# plugwatch.net
KiCad netlist of a schematic drawn in EAGLE
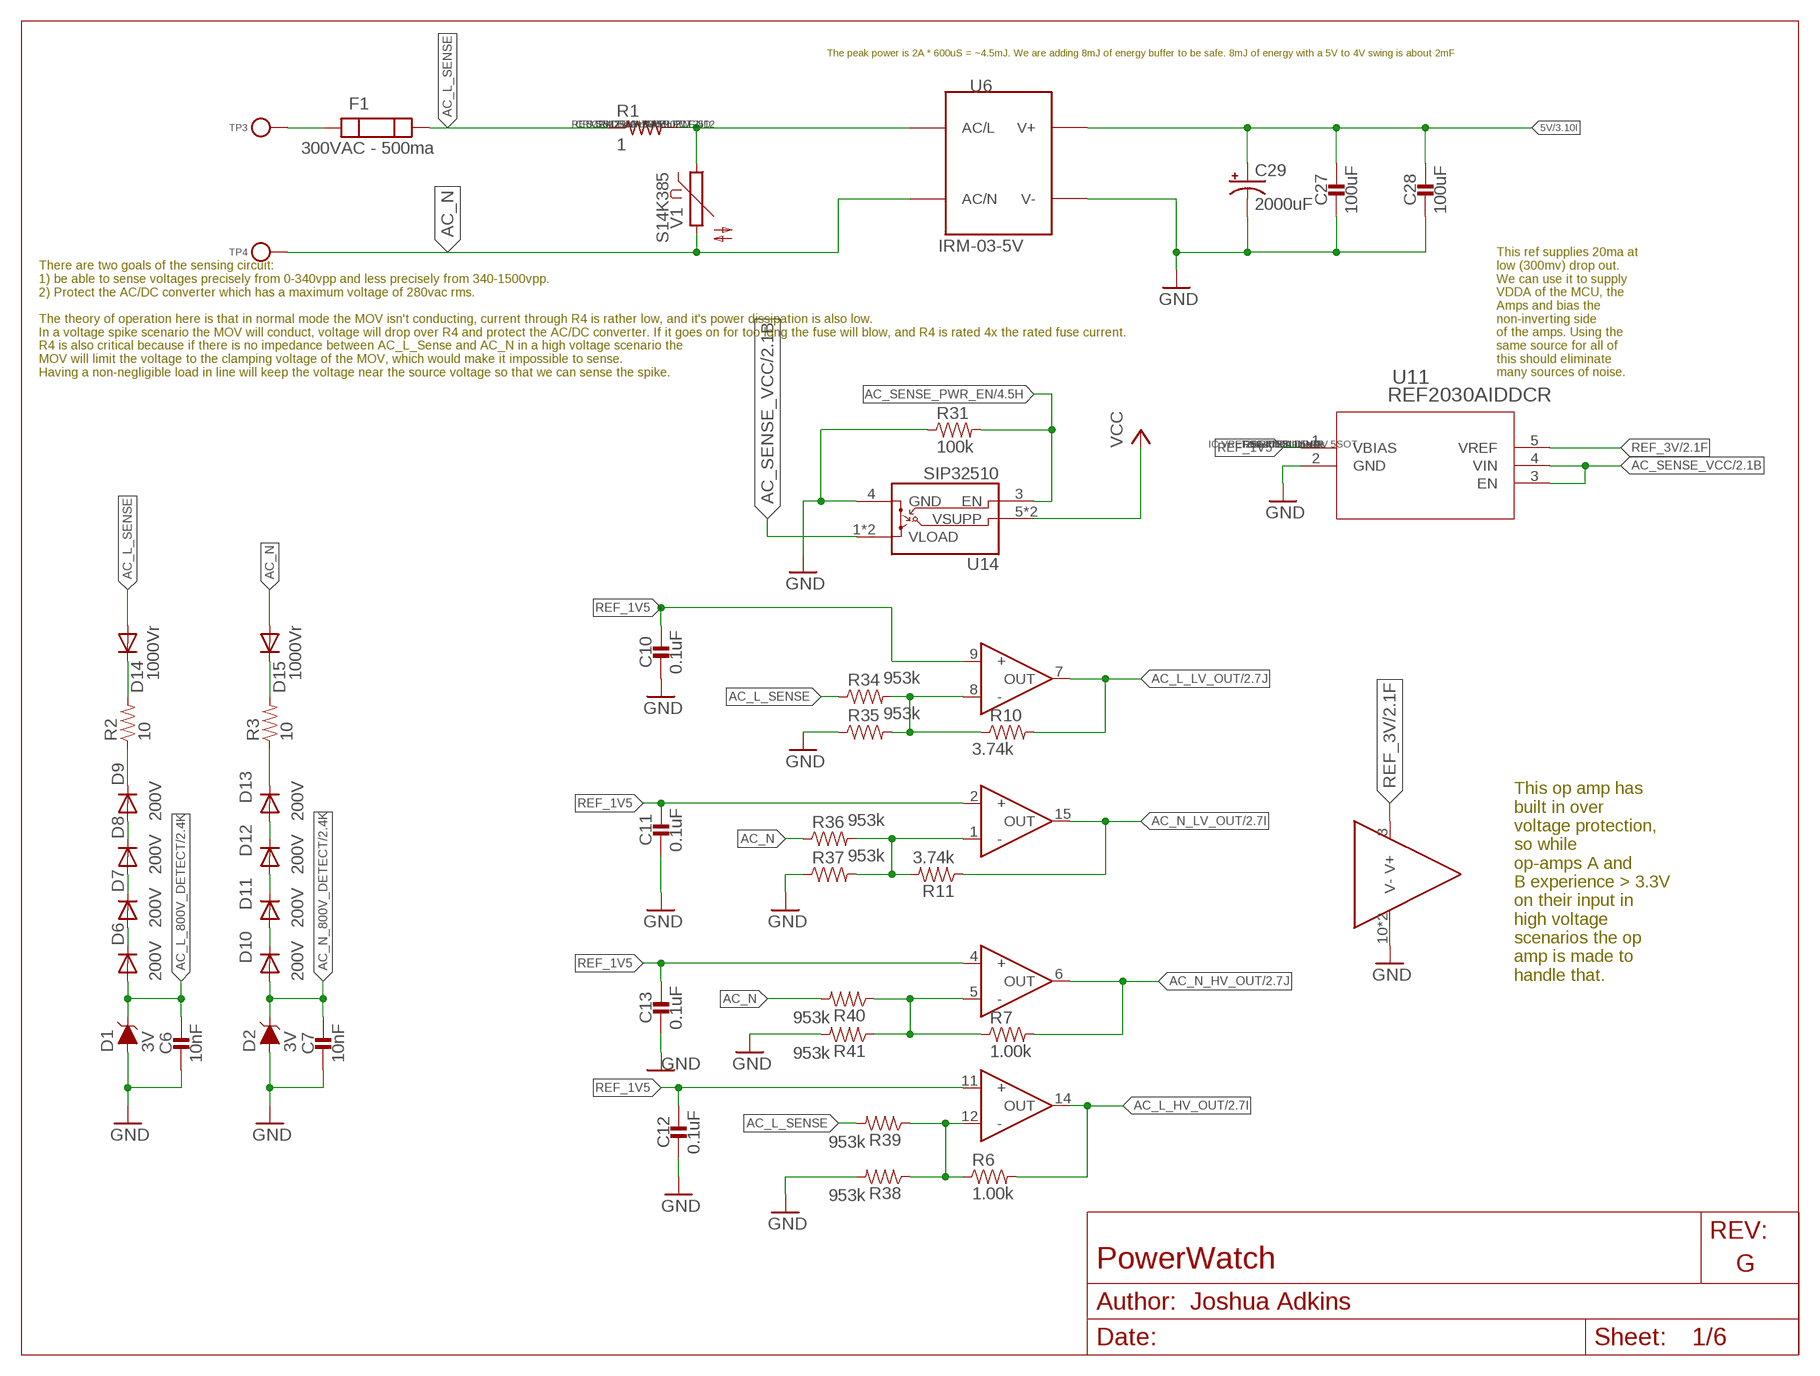
[diagram p0: schematic, sheet 1]
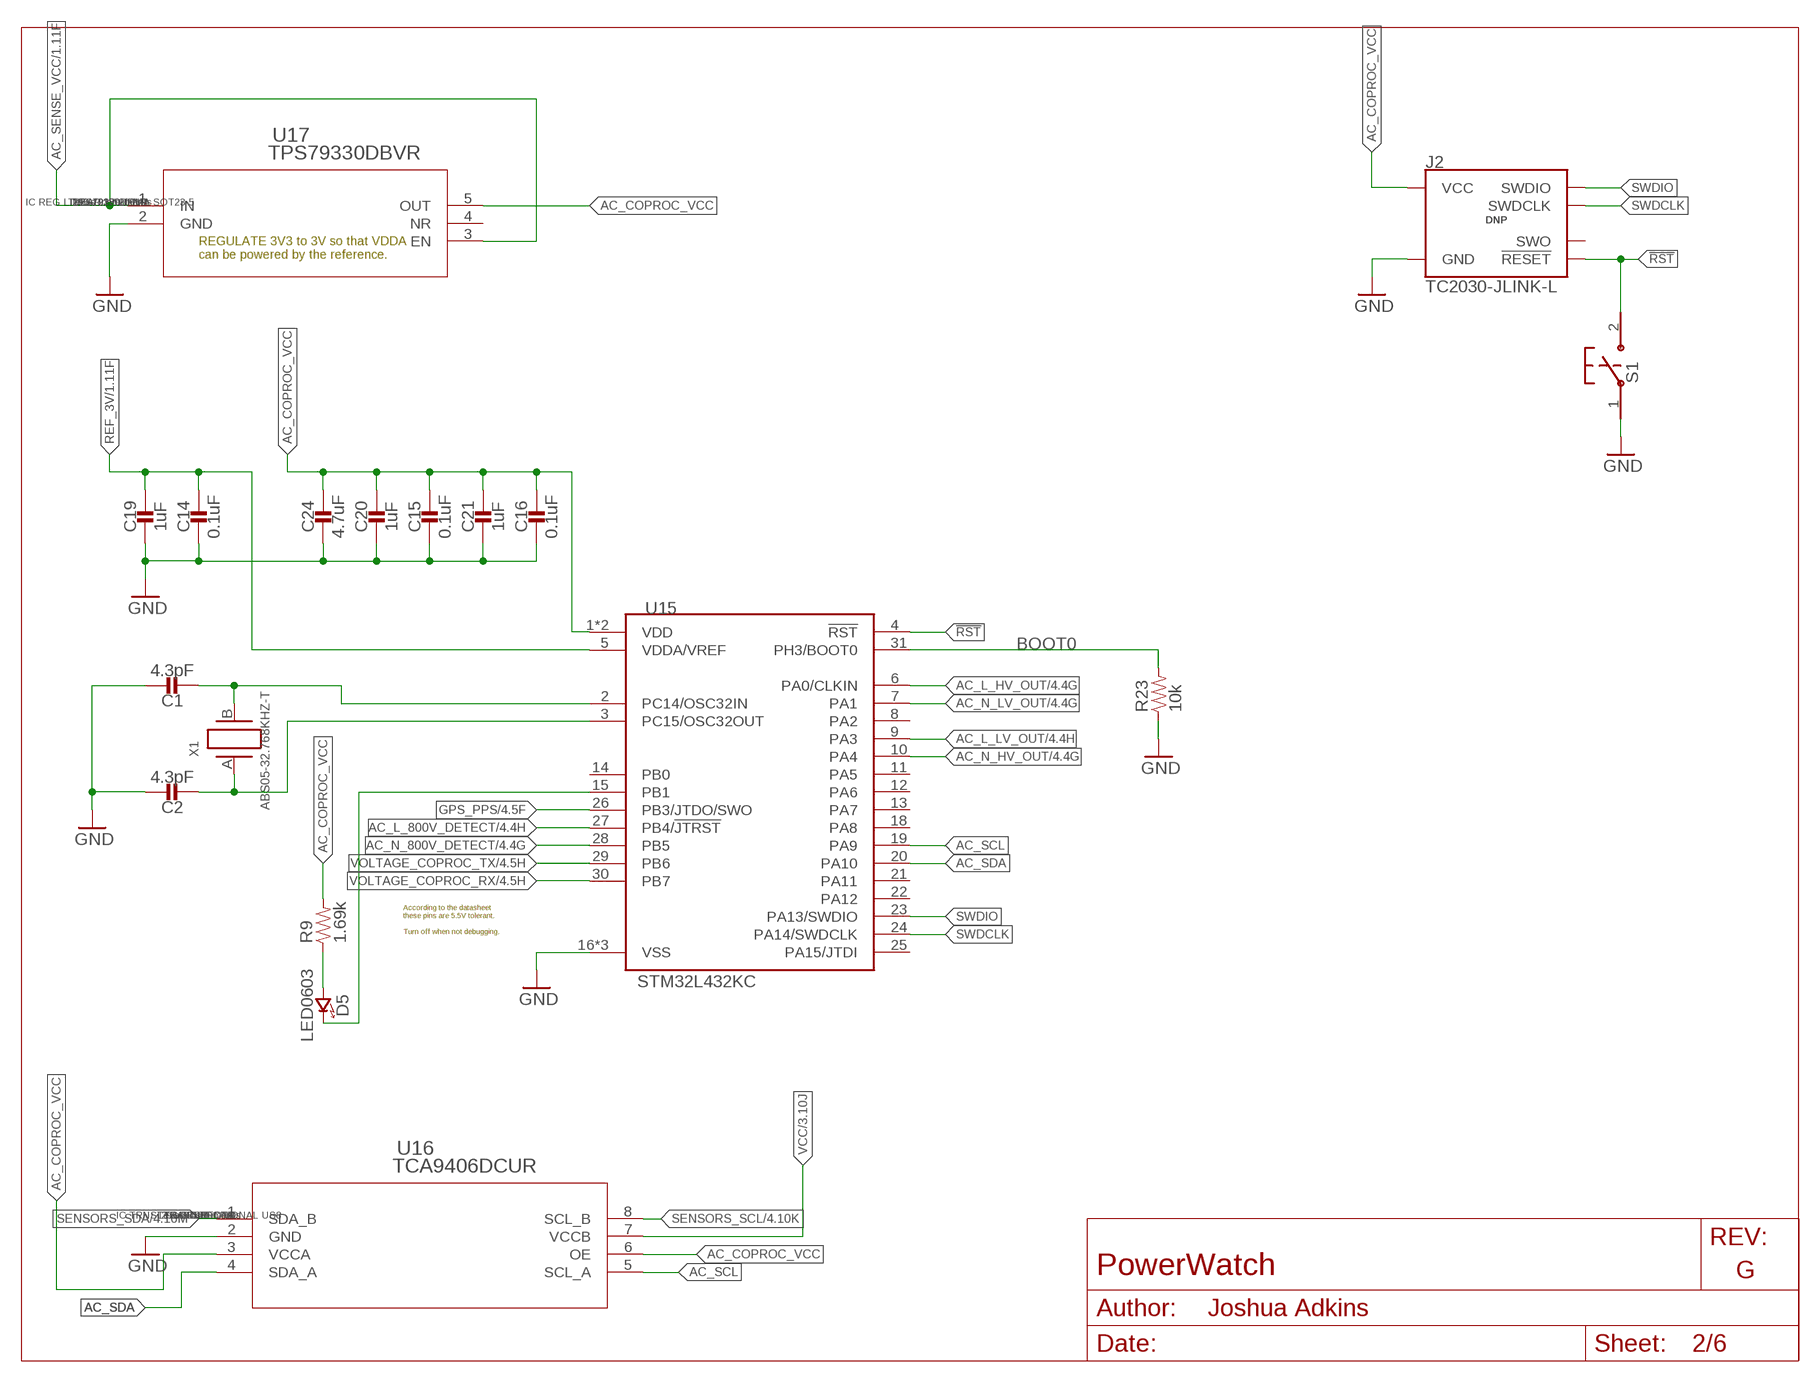
[diagram p1: schematic, sheet 2]
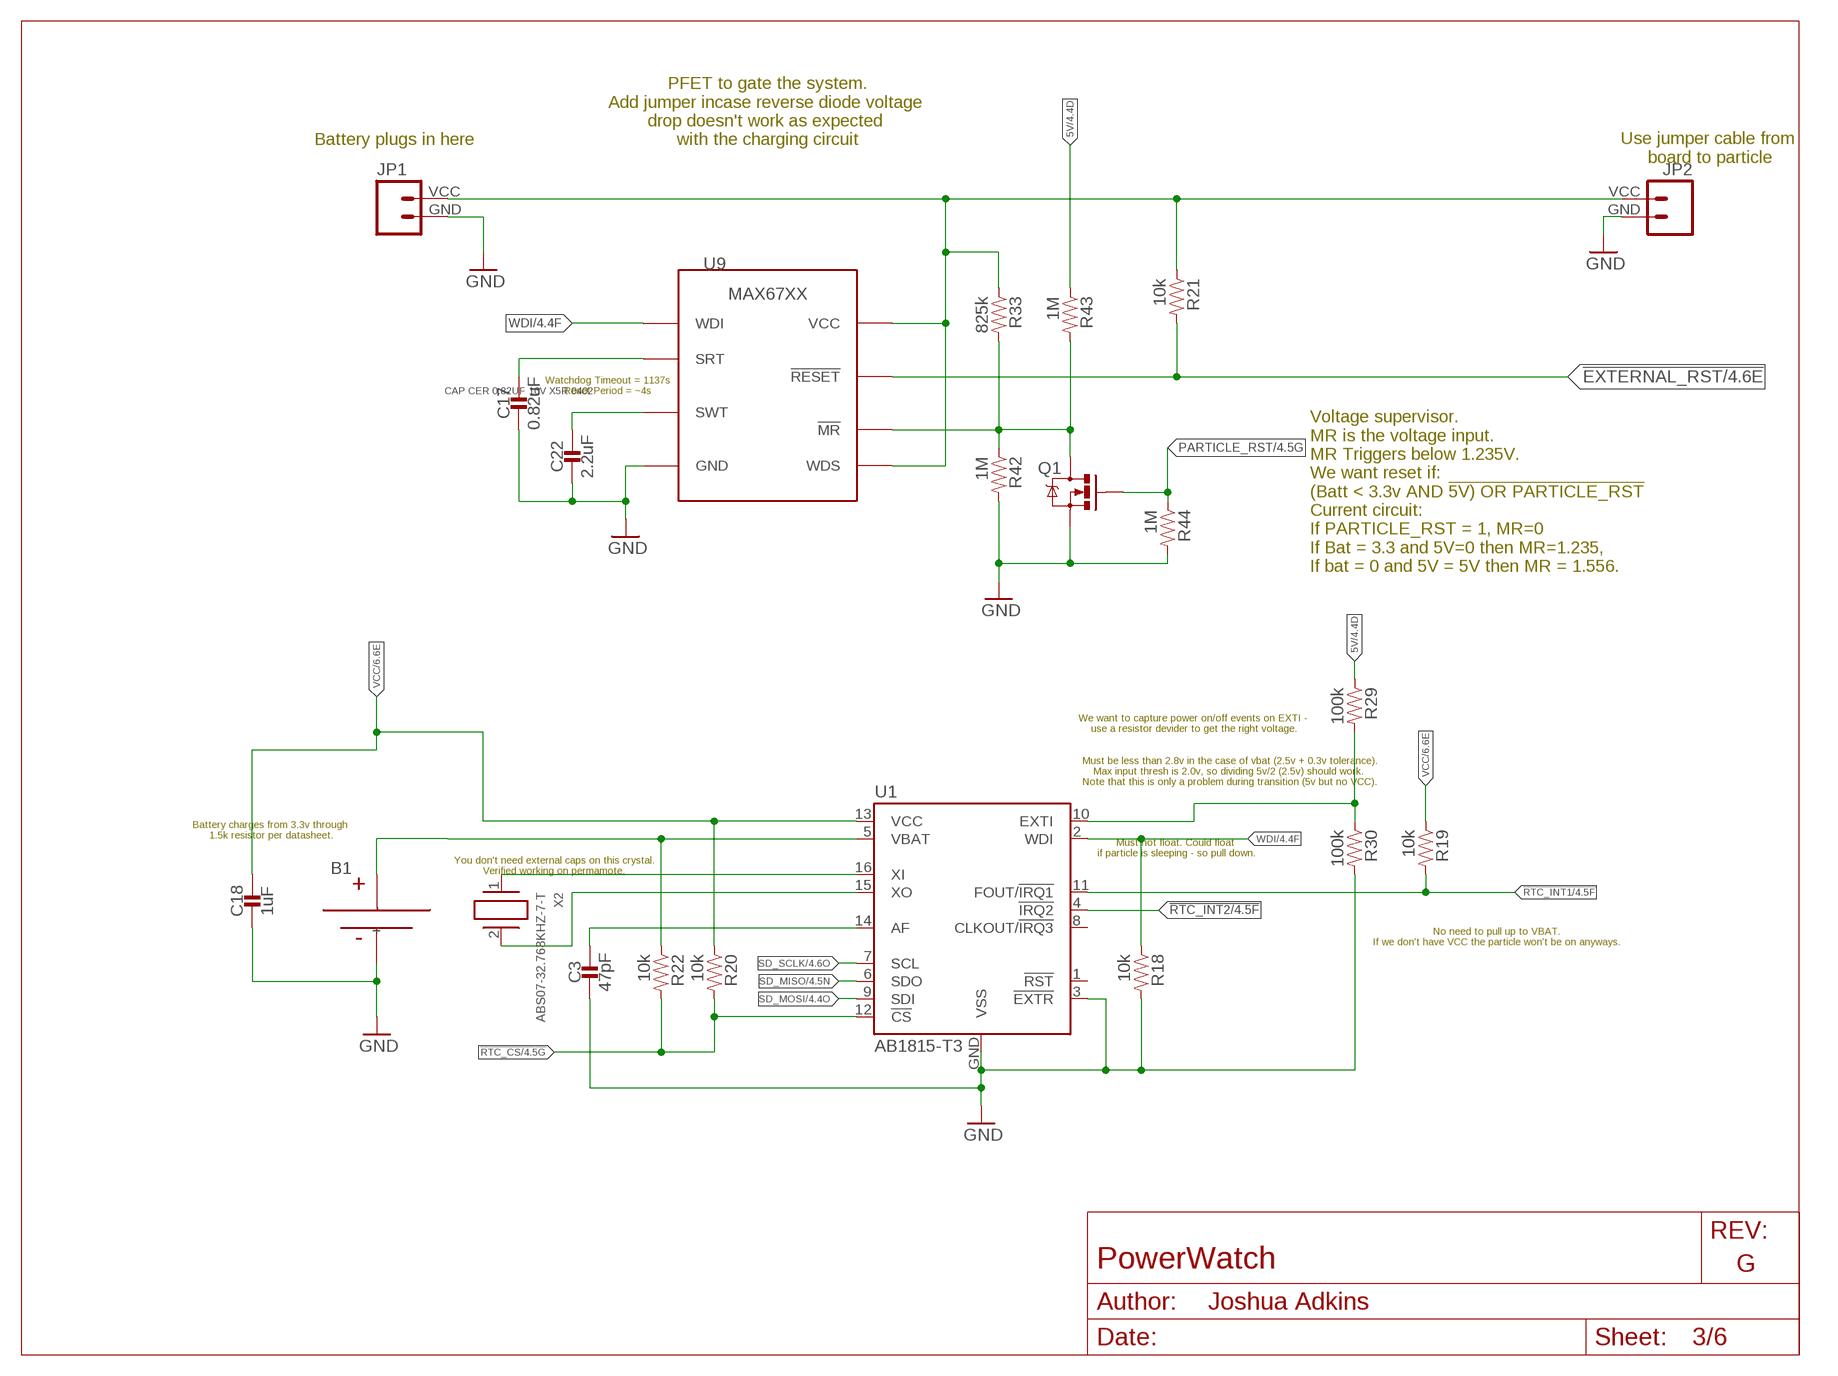
[diagram p2: schematic, sheet 3]
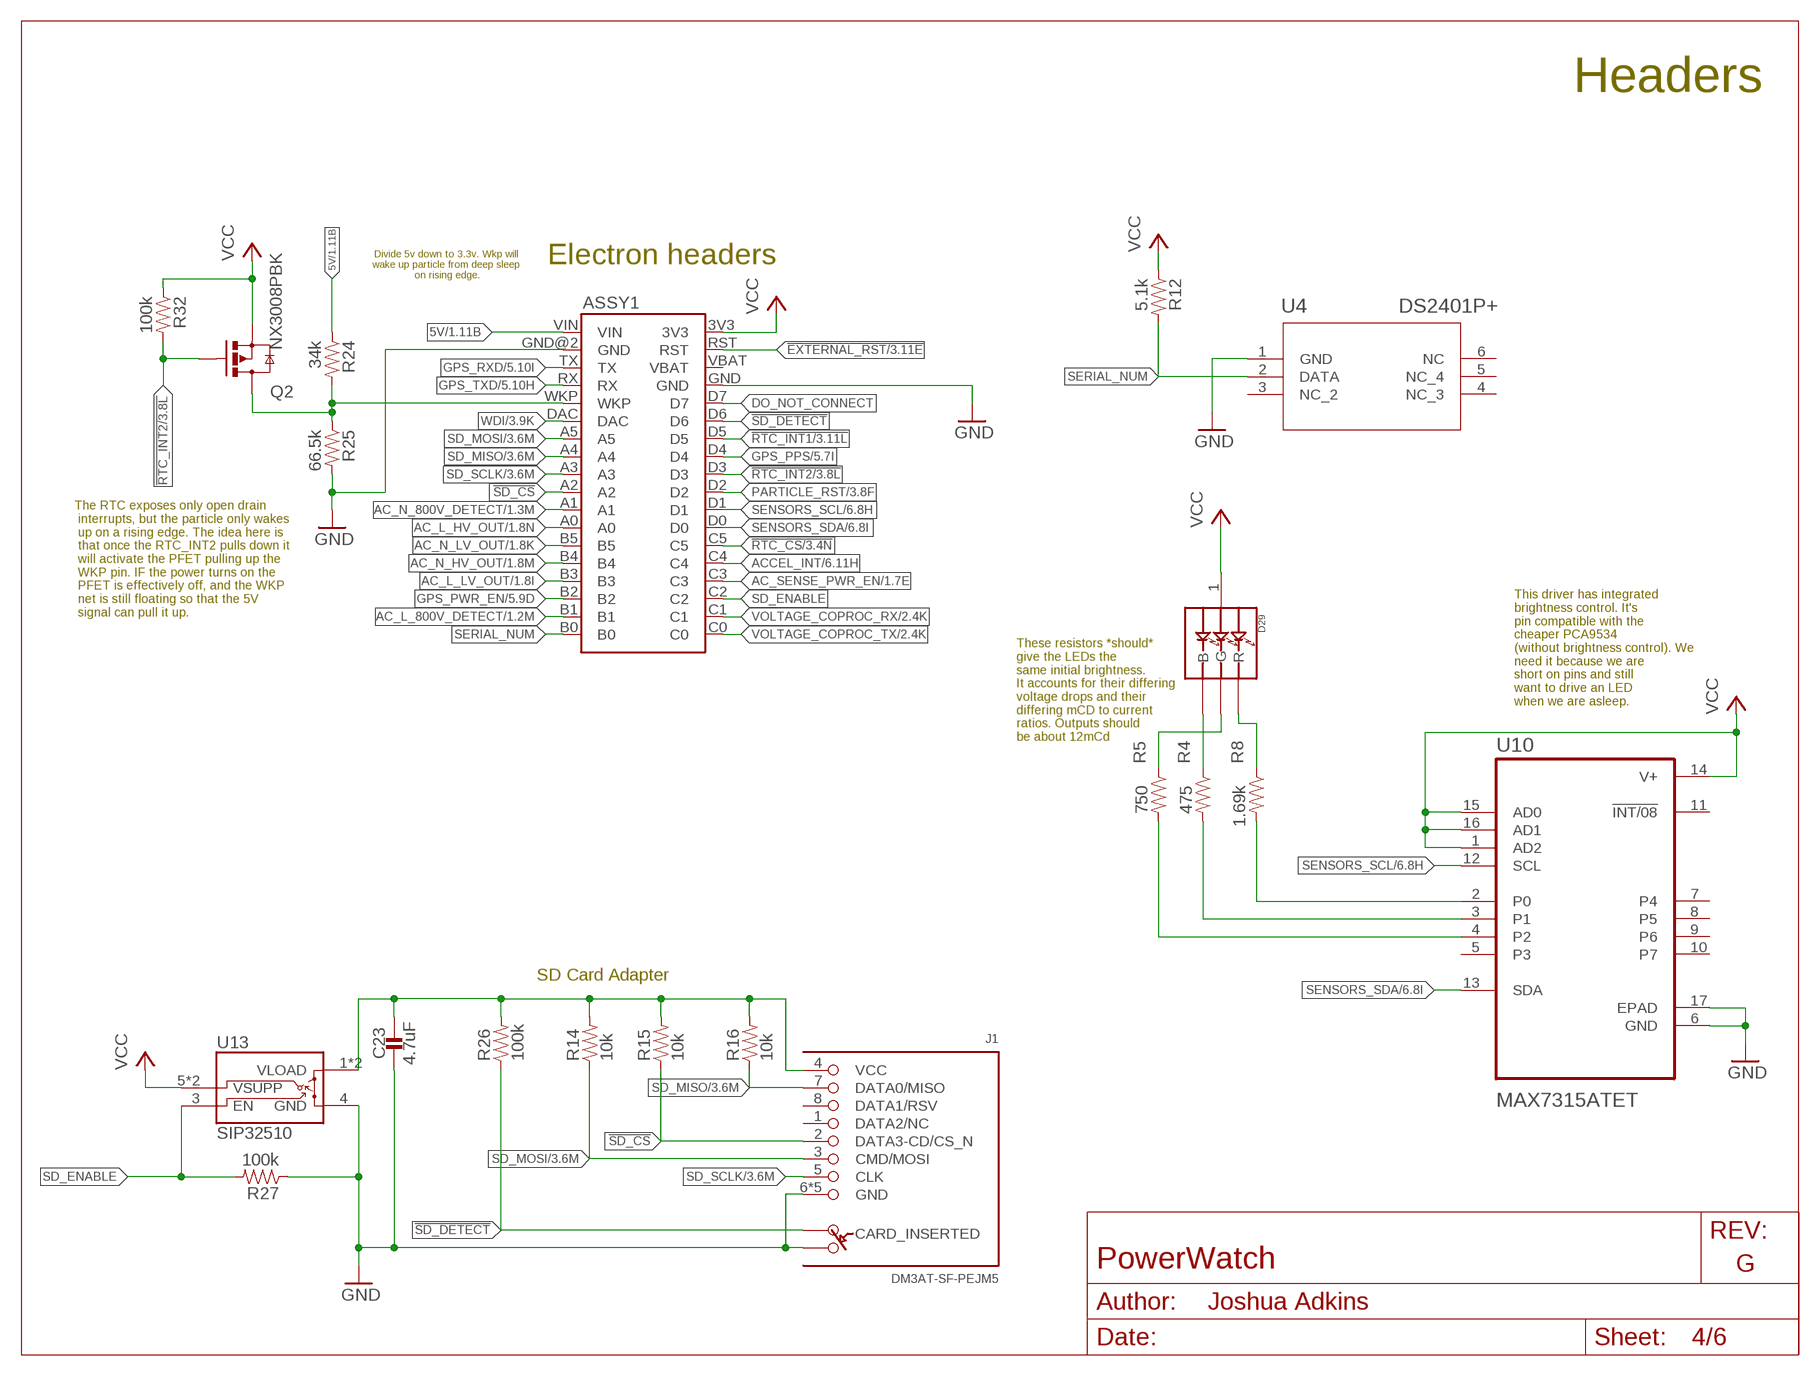
[diagram p3: schematic, sheet 4]
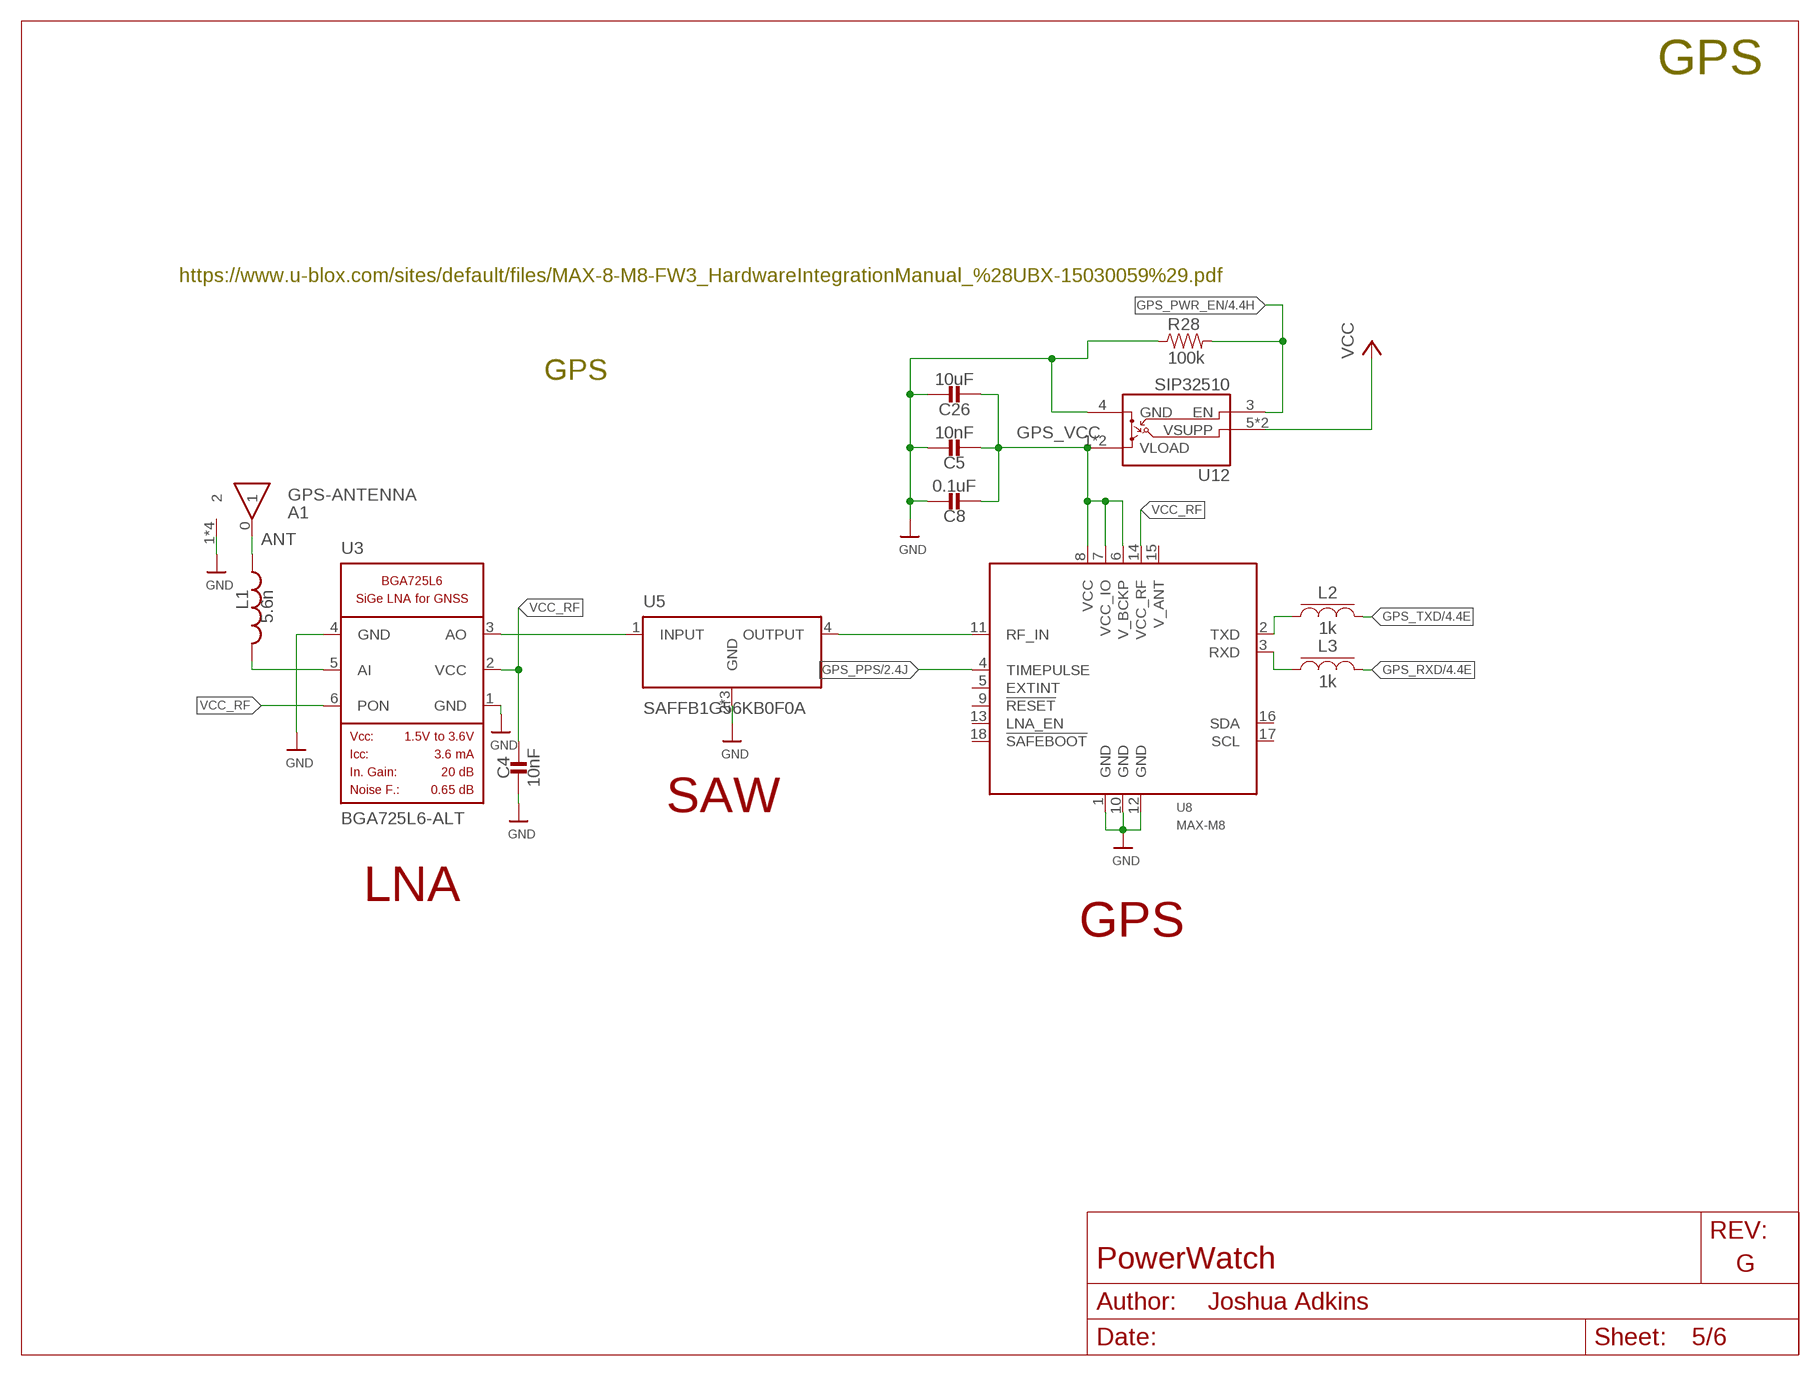
[diagram p4: schematic, sheet 5]
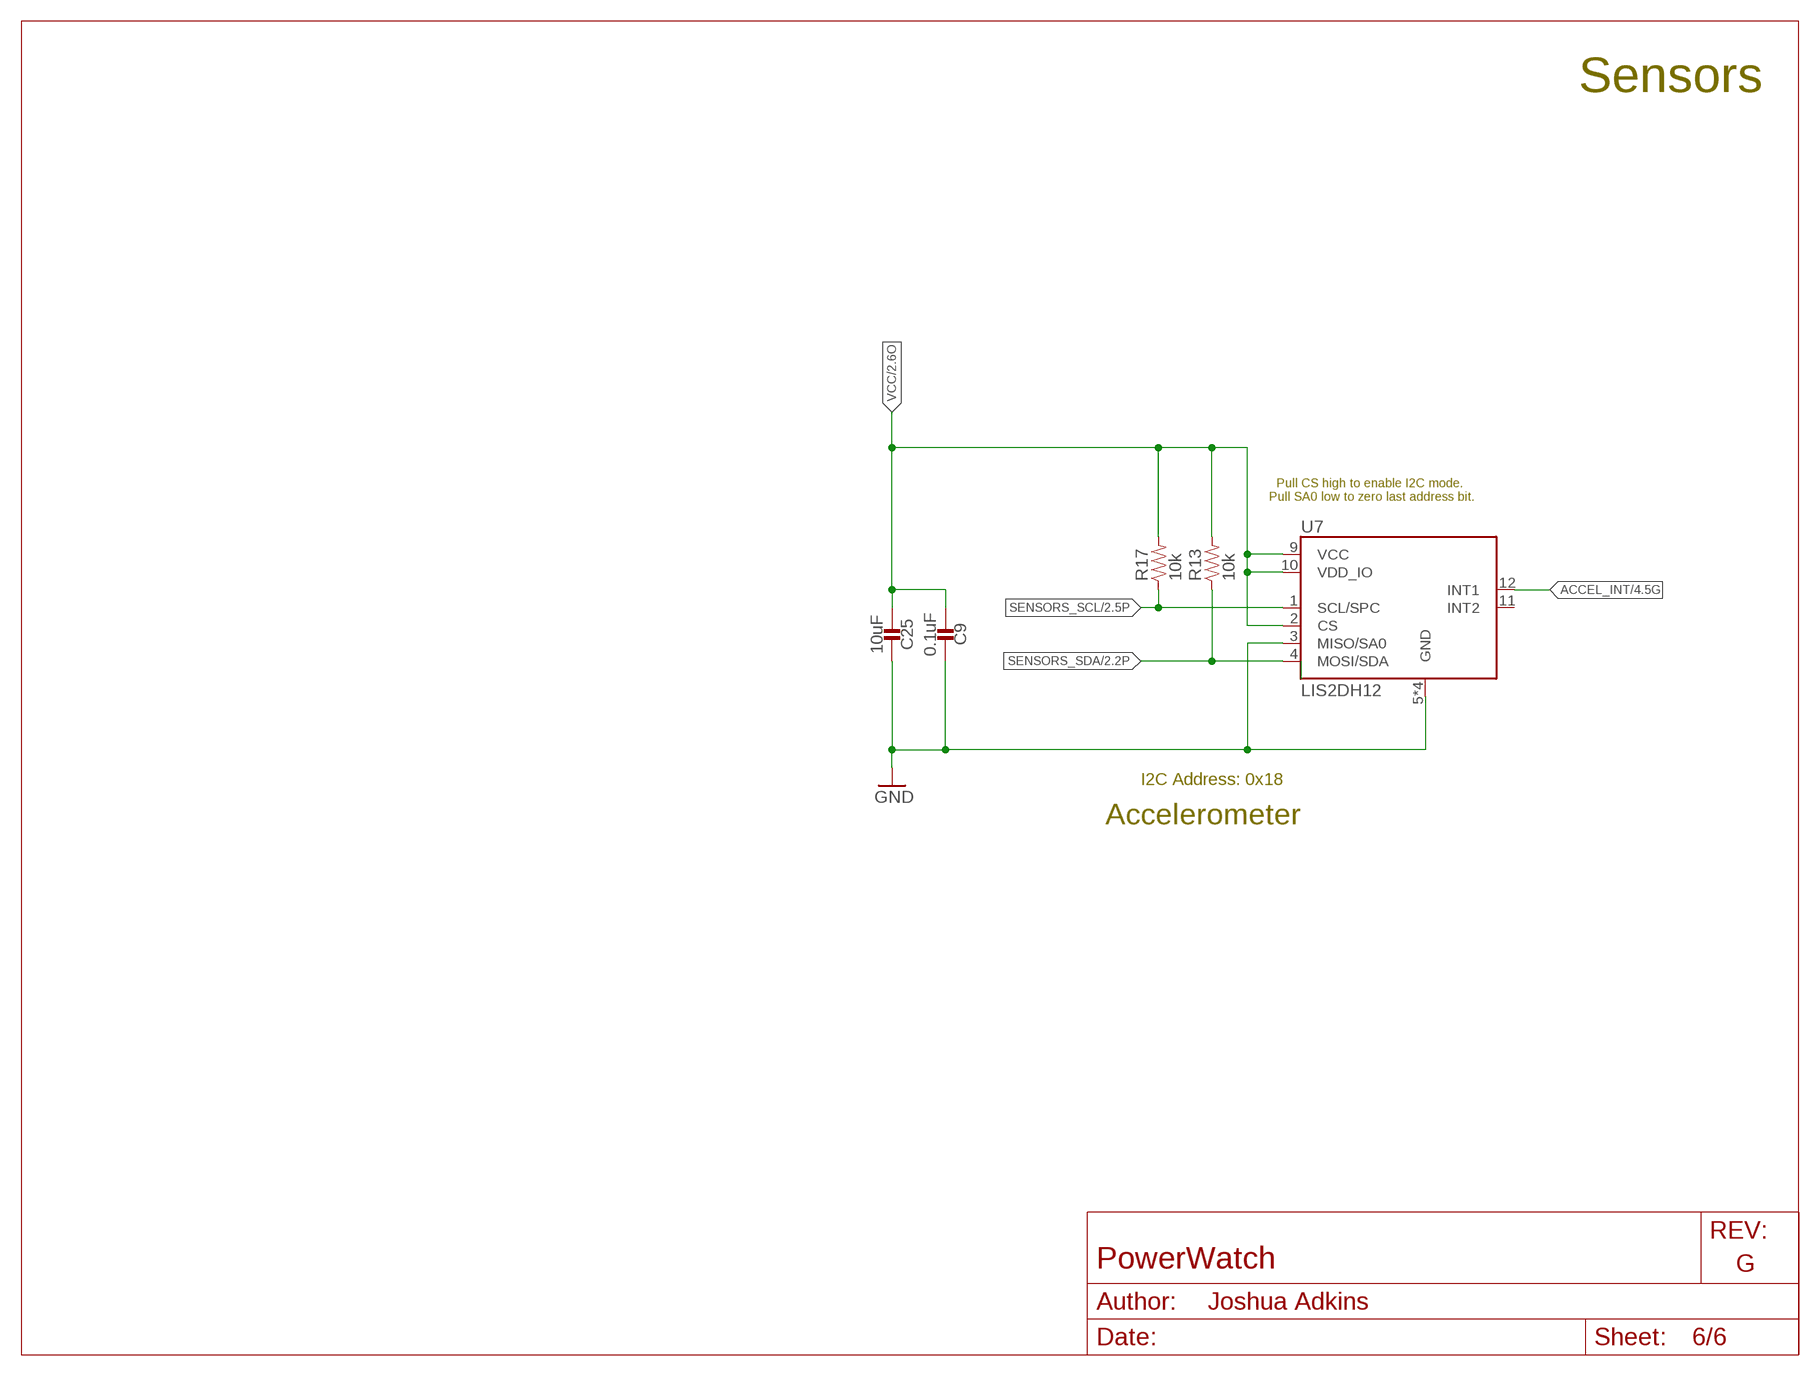
[diagram p5: schematic, sheet 6]

(export (version "E")
  (design (tool "Eeschema 10.0.6"))
  (components
    (comp (ref "A1")
      (value "GPS-ANTENNA")
      (footprint "eagle-import:ANT1818B00BT1516S")
      (description "PATCH ANT GPS/GLO CP SMD")
      (fields (field (name "MANUFACTURER") "Yageo") (field (name "MPN") "ANT1818B00BT1516S"))
      (libsource (lib "eagle-import") (part "GPS-ANTENNA"))
    )
    (comp (ref "C4")
      (value "10nF")
      (footprint "eagle-import:0402_CAP")
      (description "CAP CER 10000PF 16V X7R 0402")
      (fields
        (field (name "MANUFACTURER") "Murata Electronics North America")
        (field (name "MPN") "GRM155R71C103KA01D")
      )
      (libsource (lib "eagle-import") (part "CAPACITOR0402_CAP"))
    )
    (comp (ref "C5")
      (value "10nF")
      (footprint "eagle-import:0402_CAP")
      (description "CAP CER 10000PF 16V X7R 0402")
      (fields
        (field (name "MANUFACTURER") "Murata Electronics North America")
        (field (name "MPN") "GRM155R71C103KA01D")
      )
      (libsource (lib "eagle-import") (part "CAPACITOR0402_CAP"))
    )
    (comp (ref "C8")
      (value "0.1uF")
      (footprint "eagle-import:0402_CAP")
      (description "CAP CER 0.1UF 10V X5R 0402")
      (fields (field (name "MANUFACTURER") "Yageo") (field (name "MPN") "CC0402KRX5R6BB104"))
      (libsource (lib "eagle-import") (part "CAPACITOR0402_CAP"))
    )
    (comp (ref "C26")
      (value "10uF")
      (footprint "eagle-import:0402_CAP")
      (description "CAP CER 10UF 6.3V X5R 0402")
      (fields
        (field (name "MANUFACTURER") "Murata Electronics North America")
        (field (name "MPN") "GRJ155R60J106ME11D")
      )
      (libsource (lib "eagle-import") (part "CAPACITOR0402_CAP"))
    )
    (comp (ref "L1")
      (value "5.6n")
      (footprint "eagle-import:0402_CAP")
      (description "FIXED IND 5.6NH 1.77A 40 MOHM")
      (fields (field (name "MANUFACTURER") "Murata") (field (name "MPN") "LQW15AN5N6B80D"))
      (libsource (lib "eagle-import") (part "INDUCTOR0402"))
    )
    (comp (ref "L2")
      (value "1k")
      (footprint "eagle-import:0402_CAP")
      (description "FERRITE BEAD 1 KOHM 0402 1LN")
      (fields (field (name "MANUFACTURER") "Murata") (field (name "MPN") "BLM15HD102SN1D"))
      (libsource (lib "eagle-import") (part "FERRITE_BEAD0402"))
    )
    (comp (ref "L3")
      (value "1k")
      (footprint "eagle-import:0402_CAP")
      (description "FERRITE BEAD 1 KOHM 0402 1LN")
      (fields (field (name "MANUFACTURER") "Murata") (field (name "MPN") "BLM15HD102SN1D"))
      (libsource (lib "eagle-import") (part "FERRITE_BEAD0402"))
    )
    (comp (ref "R28")
      (value "100k")
      (footprint "eagle-import:0402_RES")
      (description "RES SMD 100K OHM 1% 1/16W 0402")
      (fields (field (name "MANUFACTURER") "Yageo") (field (name "MPN") "RC0402FR-07100KL"))
      (libsource (lib "eagle-import") (part "RESISTOR0402_RES"))
    )
    (comp (ref "U3")
      (value "BGA725L6-ALT")
      (footprint "eagle-import:LNA-TSLP-6-2-ALT")
      (description "IC AMP MMIC RF LNA 20DB TSLP-6")
      (fields (field (name "MANUFACTURER") "Infineon") (field (name "MPN") "BGA725L6E6327FTSA1"))
      (libsource (lib "eagle-import") (part "BGA725L6-ALT"))
    )
    (comp (ref "U5")
      (value "SAFFB1G56KB0F0A")
      (footprint "eagle-import:QCS5I")
      (description "FILTER SAW 1.575GHZ 5SMD")
      (fields (field (name "MANUFACTURER") "Taiyo Yuden") (field (name "MPN") "F6QA1G575H2JF-J"))
      (libsource (lib "eagle-import") (part "FILTERS"))
    )
    (comp (ref "U8")
      (value "MAX-M8")
      (footprint "eagle-import:MAX-M8")
      (description "IC RECEIVER GPS/GNSS 18LCC")
      (fields (field (name "MANUFACTURER") "u-blox") (field (name "MPN") "MAX-M8Q-0"))
      (libsource (lib "eagle-import") (part "MAX-M8"))
    )
    (comp (ref "U12")
      (value "SIP32510")
      (footprint "eagle-import:TSOT23-6")
      (fields (field (name "MANUFACTURER") "Vishay") (field (name "MPN") "SIP32510DT-T1-GE3"))
      (libsource (lib "eagle-import") (part "SIP32510"))
    )
    (comp (ref "ASSY1")
      (value "ELECTRON")
      (footprint "eagle-import:ELECTRON_SINGLE-ROW")
      (description "18 Position header")
      (fields (field (name "MANUFACTURER") "Sullins") (field (name "MPN") "PPPC181LFBN-RC"))
      (libsource (lib "eagle-import") (part "ELECTRON"))
    )
    (comp (ref "C23")
      (value "4.7uF")
      (footprint "eagle-import:0402_CAP")
      (description "CAP CER 4.7UF 6.3V X5R 0402")
      (fields (field (name "MANUFACTURER") "TDK Corporation ") (field (name "MPN") "C1005X5R0J475K050BC "))
      (libsource (lib "eagle-import") (part "CAPACITOR0402_CAP"))
    )
    (comp (ref "D29")
      (value "SML-LX0404SIUPGUSB")
      (footprint "eagle-import:1MM_SQ_4PAD")
      (fields (field (name "MANUFACTURER") "Lumex Opto"))
      (libsource (lib "eagle-import") (part "SML-LX0404SIUPGUSB"))
    )
    (comp (ref "J1")
      (value "DM3AT-SF-PEJM5")
      (footprint "eagle-import:DM3AT-SF-PEJM5")
      (fields (field (name "MANUFACTURER") "Hirose Electric Co Ltd"))
      (libsource (lib "eagle-import") (part "DM3AT-SF-PEJM5"))
    )
    (comp (ref "Q2")
      (value "NX3008PBK")
      (footprint "eagle-import:SOT23-3")
      (fields (field (name "MANUFACTURER") "Nexperia") (field (name "MPN") "NX3008PBK,215"))
      (libsource (lib "eagle-import") (part "NX3008PBK"))
    )
    (comp (ref "R4")
      (value "475")
      (footprint "eagle-import:0402_RES")
      (description "RES 475 OHM 1% 1/16W 0402")
      (fields (field (name "MANUFACTURER") "Stackpole Electronics Inc") (field (name "MPN") "RMCF0402FT475R"))
      (libsource (lib "eagle-import") (part "RESISTOR0402_RES"))
    )
    (comp (ref "R5")
      (value "750")
      (footprint "eagle-import:0402_RES")
      (description "RES SMD 750 OHM 1% 1/10W 0402")
      (fields
        (field (name "MANUFACTURER") "Panasonic Electronic Components")
        (field (name "MPN") "ERJ-2RKF7500X")
      )
      (libsource (lib "eagle-import") (part "RESISTOR0402_RES"))
    )
    (comp (ref "R8")
      (value "1.69k")
      (footprint "eagle-import:0402_RES")
      (description "RES SMD 1.69K OHM 1% 1/16W 0402")
      (fields (field (name "MANUFACTURER") "Yageo") (field (name "MPN") "RC0402FR-071K69L"))
      (libsource (lib "eagle-import") (part "RESISTOR0402_RES"))
    )
    (comp (ref "R12")
      (value "5.1k")
      (footprint "eagle-import:0402_RES")
      (description "RES SMD 5.1K OHM 1% 1/10W 0402")
      (fields
        (field (name "MANUFACTURER") "Panasonic Electronic Components")
        (field (name "MPN") "ERJ-2RKF5101X")
      )
      (libsource (lib "eagle-import") (part "RESISTOR0402_RES"))
    )
    (comp (ref "R14")
      (value "10k")
      (footprint "eagle-import:0402_RES")
      (description "RES SMD 10K OHM 1% 1/16W 0402")
      (fields
        (field (name "MANUFACTURER") "Stackpole Electronics Inc. ")
        (field (name "MPN") "RMCF0402FT10K0 ")
      )
      (libsource (lib "eagle-import") (part "RESISTOR0402_RES"))
    )
    (comp (ref "R15")
      (value "10k")
      (footprint "eagle-import:0402_RES")
      (description "RES SMD 10K OHM 1% 1/16W 0402")
      (fields
        (field (name "MANUFACTURER") "Stackpole Electronics Inc. ")
        (field (name "MPN") "RMCF0402FT10K0 ")
      )
      (libsource (lib "eagle-import") (part "RESISTOR0402_RES"))
    )
    (comp (ref "R16")
      (value "10k")
      (footprint "eagle-import:0402_RES")
      (description "RES SMD 10K OHM 1% 1/16W 0402")
      (fields
        (field (name "MANUFACTURER") "Stackpole Electronics Inc. ")
        (field (name "MPN") "RMCF0402FT10K0 ")
      )
      (libsource (lib "eagle-import") (part "RESISTOR0402_RES"))
    )
    (comp (ref "R24")
      (value "34k")
      (footprint "eagle-import:0402_RES")
      (description "RES SMD 34K OHM 1% 1/10W 0402")
      (fields
        (field (name "MANUFACTURER") "Panasonic Electronic Components")
        (field (name "MPN") "ERJ-2RKF3402X")
      )
      (libsource (lib "eagle-import") (part "RESISTOR0402_RES"))
    )
    (comp (ref "R25")
      (value "66.5k")
      (footprint "eagle-import:0402_RES")
      (description "RES SMD 66.5K OHM 1% 1/16W 0402")
      (fields (field (name "MANUFACTURER") "Yageo") (field (name "MPN") "RC0402FR-0766K5L"))
      (libsource (lib "eagle-import") (part "RESISTOR0402_RES"))
    )
    (comp (ref "R26")
      (value "100k")
      (footprint "eagle-import:0402_RES")
      (description "RES SMD 100K OHM 1% 1/16W 0402")
      (fields (field (name "MANUFACTURER") "Yageo") (field (name "MPN") "RC0402FR-07100KL"))
      (libsource (lib "eagle-import") (part "RESISTOR0402_RES"))
    )
    (comp (ref "R27")
      (value "100k")
      (footprint "eagle-import:0402_RES")
      (description "RES SMD 100K OHM 1% 1/16W 0402")
      (fields (field (name "MANUFACTURER") "Yageo") (field (name "MPN") "RC0402FR-07100KL"))
      (libsource (lib "eagle-import") (part "RESISTOR0402_RES"))
    )
    (comp (ref "R32")
      (value "100k")
      (footprint "eagle-import:0402_RES")
      (description "RES SMD 100K OHM 1% 1/16W 0402")
      (fields (field (name "MANUFACTURER") "Yageo") (field (name "MPN") "RC0402FR-07100KL"))
      (libsource (lib "eagle-import") (part "RESISTOR0402_RES"))
    )
    (comp (ref "U4")
      (value "DS2401P+")
      (footprint "eagle-import:21-0382")
      (fields (field (name "MANUFACTURER") "Maxim Integrated") (field (name "SPICEPREFIX") "X"))
      (libsource (lib "eagle-import") (part "DS2401P+"))
    )
    (comp (ref "U10")
      (value "MAX7315ATET")
      (footprint "eagle-import:QFN50P300X300X80-17N")
      (description "IC I/O EXPANDER I2C 8B 16TQFN")
      (fields
        (field (name "DIGI-KEY_PART_NUMBER") "MAX7315ATE+-ND")
        (field (name "MF") "Maxim Integrated")
        (field (name "MP") "MAX7315ATE+")
        (field (name "DIGIKEY") "MAX7315ATE+-ND")
        (field (name "MANUFACTURER") "Maxim Integrated")
        (field (name "MPN") "MAX7315ATE+")
      )
      (libsource (lib "eagle-import") (part "MAX7315ATET"))
    )
    (comp (ref "U13")
      (value "SIP32510")
      (footprint "eagle-import:TSOT23-6")
      (fields (field (name "MANUFACTURER") "Vishay") (field (name "MPN") "SIP32510DT-T1-GE3"))
      (libsource (lib "eagle-import") (part "SIP32510"))
    )
    (comp (ref "C6")
      (value "10nF")
      (footprint "eagle-import:0402_CAP")
      (description "CAP CER 10000PF 16V X7R 0402")
      (fields
        (field (name "MANUFACTURER") "Murata Electronics North America")
        (field (name "MPN") "GRM155R71C103KA01D")
      )
      (libsource (lib "eagle-import") (part "CAPACITOR0402_CAP"))
    )
    (comp (ref "C7")
      (value "10nF")
      (footprint "eagle-import:0402_CAP")
      (description "CAP CER 10000PF 16V X7R 0402")
      (fields
        (field (name "MANUFACTURER") "Murata Electronics North America")
        (field (name "MPN") "GRM155R71C103KA01D")
      )
      (libsource (lib "eagle-import") (part "CAPACITOR0402_CAP"))
    )
    (comp (ref "C10")
      (value "0.1uF")
      (footprint "eagle-import:0402_CAP")
      (description "CAP CER 0.1UF 10V X5R 0402")
      (fields (field (name "MANUFACTURER") "Yageo") (field (name "MPN") "CC0402KRX5R6BB104"))
      (libsource (lib "eagle-import") (part "CAPACITOR0402_CAP"))
    )
    (comp (ref "C11")
      (value "0.1uF")
      (footprint "eagle-import:0402_CAP")
      (description "CAP CER 0.1UF 10V X5R 0402")
      (fields (field (name "MANUFACTURER") "Yageo") (field (name "MPN") "CC0402KRX5R6BB104"))
      (libsource (lib "eagle-import") (part "CAPACITOR0402_CAP"))
    )
    (comp (ref "C12")
      (value "0.1uF")
      (footprint "eagle-import:0402_CAP")
      (description "CAP CER 0.1UF 10V X5R 0402")
      (fields (field (name "MANUFACTURER") "Yageo") (field (name "MPN") "CC0402KRX5R6BB104"))
      (libsource (lib "eagle-import") (part "CAPACITOR0402_CAP"))
    )
    (comp (ref "C13")
      (value "0.1uF")
      (footprint "eagle-import:0402_CAP")
      (description "CAP CER 0.1UF 10V X5R 0402")
      (fields (field (name "MANUFACTURER") "Yageo") (field (name "MPN") "CC0402KRX5R6BB104"))
      (libsource (lib "eagle-import") (part "CAPACITOR0402_CAP"))
    )
    (comp (ref "C27")
      (value "100uF")
      (footprint "eagle-import:1210_CAP")
      (description "CAP CER 100UF 6.3V X7S 1210")
      (fields
        (field (name "MANUFACTURER") "Murata Electronics North America")
        (field (name "MPN") "GRM32EC70J107ME15L")
      )
      (libsource (lib "eagle-import") (part "CAPACITOR1210_CAP"))
    )
    (comp (ref "C28")
      (value "100uF")
      (footprint "eagle-import:1210_CAP")
      (description "CAP CER 100UF 6.3V X7S 1210")
      (fields
        (field (name "MANUFACTURER") "Murata Electronics North America")
        (field (name "MPN") "GRM32EC70J107ME15L")
      )
      (libsource (lib "eagle-import") (part "CAPACITOR1210_CAP"))
    )
    (comp (ref "C29")
      (value "2000uF")
      (footprint "eagle-import:E5-10,5")
      (description "CAP ALUM 2000UF 20% 6.3V T/H")
      (fields
        (field (name "MANUFACTURER") "Panasonic Electronic Components")
        (field (name "MPN") "EEU-FS0J202B")
      )
      (libsource (lib "eagle-import") (part "CPOL-USE5-10.5"))
    )
    (comp (ref "D1")
      (value "3V")
      (footprint "eagle-import:SOD-323")
      (description "DIODE ZENER 3V 300MW SOD323")
      (fields
        (field (name "DIGIKEY") "MM3Z3V0ST1GOSCT-ND")
        (field (name "MANUFACTURER") "ON Semiconductor")
        (field (name "MPN") "MM3Z3V0ST1G")
      )
      (libsource (lib "eagle-import") (part "DIODE-ZENER-MM3Z3V3T1G"))
    )
    (comp (ref "D2")
      (value "3V")
      (footprint "eagle-import:SOD-323")
      (description "DIODE ZENER 3V 300MW SOD323")
      (fields
        (field (name "DIGIKEY") "MM3Z3V0ST1GOSCT-ND")
        (field (name "MANUFACTURER") "ON Semiconductor")
        (field (name "MPN") "MM3Z3V0ST1G")
      )
      (libsource (lib "eagle-import") (part "DIODE-ZENER-MM3Z3V3T1G"))
    )
    (comp (ref "D6")
      (value "200V")
      (footprint "eagle-import:DO214AA")
      (description "DIODE ZENER 200V 3W DO214AA")
      (fields
        (field (name "DIGIKEY") "1PGSMB5956R5GCT-ND")
        (field (name "MANUFACTURER") "Taiwan Semiconductor Corporation")
        (field (name "MPN") "1PGSMB5956 R5G")
      )
      (libsource (lib "eagle-import") (part "DIODE-DO214AA"))
    )
    (comp (ref "D7")
      (value "200V")
      (footprint "eagle-import:DO214AA")
      (description "DIODE ZENER 200V 3W DO214AA")
      (fields
        (field (name "DIGIKEY") "1PGSMB5956R5GCT-ND")
        (field (name "MANUFACTURER") "Taiwan Semiconductor Corporation")
        (field (name "MPN") "1PGSMB5956 R5G")
      )
      (libsource (lib "eagle-import") (part "DIODE-DO214AA"))
    )
    (comp (ref "D8")
      (value "200V")
      (footprint "eagle-import:DO214AA")
      (description "DIODE ZENER 200V 3W DO214AA")
      (fields
        (field (name "DIGIKEY") "1PGSMB5956R5GCT-ND")
        (field (name "MANUFACTURER") "Taiwan Semiconductor Corporation")
        (field (name "MPN") "1PGSMB5956 R5G")
      )
      (libsource (lib "eagle-import") (part "DIODE-DO214AA"))
    )
    (comp (ref "D9")
      (value "200V")
      (footprint "eagle-import:DO214AA")
      (description "DIODE ZENER 200V 3W DO214AA")
      (fields
        (field (name "DIGIKEY") "1PGSMB5956R5GCT-ND")
        (field (name "MANUFACTURER") "Taiwan Semiconductor Corporation")
        (field (name "MPN") "1PGSMB5956 R5G")
      )
      (libsource (lib "eagle-import") (part "DIODE-DO214AA"))
    )
    (comp (ref "D10")
      (value "200V")
      (footprint "eagle-import:DO214AA")
      (description "DIODE ZENER 200V 3W DO214AA")
      (fields
        (field (name "DIGIKEY") "1PGSMB5956R5GCT-ND")
        (field (name "MANUFACTURER") "Taiwan Semiconductor Corporation")
        (field (name "MPN") "1PGSMB5956 R5G")
      )
      (libsource (lib "eagle-import") (part "DIODE-DO214AA"))
    )
    (comp (ref "D11")
      (value "200V")
      (footprint "eagle-import:DO214AA")
      (description "DIODE ZENER 200V 3W DO214AA")
      (fields
        (field (name "DIGIKEY") "1PGSMB5956R5GCT-ND")
        (field (name "MANUFACTURER") "Taiwan Semiconductor Corporation")
        (field (name "MPN") "1PGSMB5956 R5G")
      )
      (libsource (lib "eagle-import") (part "DIODE-DO214AA"))
    )
    (comp (ref "D12")
      (value "200V")
      (footprint "eagle-import:DO214AA")
      (description "DIODE ZENER 200V 3W DO214AA")
      (fields
        (field (name "DIGIKEY") "1PGSMB5956R5GCT-ND")
        (field (name "MANUFACTURER") "Taiwan Semiconductor Corporation")
        (field (name "MPN") "1PGSMB5956 R5G")
      )
      (libsource (lib "eagle-import") (part "DIODE-DO214AA"))
    )
    (comp (ref "D13")
      (value "200V")
      (footprint "eagle-import:DO214AA")
      (description "DIODE ZENER 200V 3W DO214AA")
      (fields
        (field (name "DIGIKEY") "1PGSMB5956R5GCT-ND")
        (field (name "MANUFACTURER") "Taiwan Semiconductor Corporation")
        (field (name "MPN") "1PGSMB5956 R5G")
      )
      (libsource (lib "eagle-import") (part "DIODE-DO214AA"))
    )
    (comp (ref "D14")
      (value "1000Vr")
      (footprint "eagle-import:DO214AC")
      (description "DIODE GEN PURP 1KV 1A SMA")
      (fields
        (field (name "DIGIKEY") "S1M-FDICT-ND")
        (field (name "MANUFACTURER") "Diodes Incorporated")
        (field (name "MPN") "S1M-13-F")
      )
      (libsource (lib "eagle-import") (part "DIODE-DO214AC"))
    )
    (comp (ref "D15")
      (value "1000Vr")
      (footprint "eagle-import:DO214AC")
      (description "DIODE GEN PURP 1KV 1A SMA")
      (fields
        (field (name "DIGIKEY") "S1M-FDICT-ND")
        (field (name "MANUFACTURER") "Diodes Incorporated")
        (field (name "MPN") "S1M-13-F")
      )
      (libsource (lib "eagle-import") (part "DIODE-DO214AC"))
    )
    (comp (ref "F1")
      (value "300VAC - 500ma")
      (footprint "eagle-import:MIRCRO_FUSE_5MM")
      (description "FUSE BRD MNT 500MA 350VAC 100VDC")
      (fields (field (name "MANUFACTURER") "Bel Fuse Inc") (field (name "MPN") "0697H0500-01"))
      (libsource (lib "eagle-import") (part "MICRO_FUSE500MA_350VAC"))
    )
    (comp (ref "R1")
      (value "1")
      (footprint "eagle-import:R2512")
      (description "RES SMD 1 OHM 5% 2W 2512")
      (fields
        (field (name "DIGIKEY") "CRM2512-JW-1R0ELFCT-ND")
        (field (name "MANUFACTURER") "Bourns Inc.")
        (field (name "MPN") "CRM2512-JW-1R0ELF")
      )
      (libsource (lib "eagle-import") (part "R-US_R2512"))
    )
    (comp (ref "R2")
      (value "10")
      (footprint "eagle-import:0402_RES")
      (description "RES SMD 10 OHM 1% 1/16W 0402")
      (fields (field (name "MANUFACTURER") "Yageo") (field (name "MPN") "RC0402FR-0710RL"))
      (libsource (lib "eagle-import") (part "RESISTOR0402_RES"))
    )
    (comp (ref "R3")
      (value "10")
      (footprint "eagle-import:0402_RES")
      (description "RES SMD 10 OHM 1% 1/16W 0402")
      (fields (field (name "MANUFACTURER") "Yageo") (field (name "MPN") "RC0402FR-0710RL"))
      (libsource (lib "eagle-import") (part "RESISTOR0402_RES"))
    )
    (comp (ref "R6")
      (value "1.00k")
      (footprint "eagle-import:0402_RES")
      (description "RES SMD 1K OHM 0.1% 1/16W 0402")
      (fields (field (name "MANUFACTURER") "Yageo") (field (name "MPN") "RT0402BRE071KL"))
      (libsource (lib "eagle-import") (part "RESISTOR0402_RES"))
    )
    (comp (ref "R7")
      (value "1.00k")
      (footprint "eagle-import:0402_RES")
      (description "RES SMD 1K OHM 0.1% 1/16W 0402")
      (fields (field (name "MANUFACTURER") "Yageo") (field (name "MPN") "RT0402BRE071KL"))
      (libsource (lib "eagle-import") (part "RESISTOR0402_RES"))
    )
    (comp (ref "R10")
      (value "3.74k")
      (footprint "eagle-import:0402_RES")
      (description "RES SMD 3.74KOHM 0.1% 1/16W 0402")
      (fields
        (field (name "MANUFACTURER") "Panasonic Electronic Components")
        (field (name "MPN") "ERA-2AEB3741X")
      )
      (libsource (lib "eagle-import") (part "RESISTOR0402_RES"))
    )
    (comp (ref "R11")
      (value "3.74k")
      (footprint "eagle-import:0402_RES")
      (description "RES SMD 3.74KOHM 0.1% 1/16W 0402")
      (fields
        (field (name "MANUFACTURER") "Panasonic Electronic Components")
        (field (name "MPN") "ERA-2AEB3741X")
      )
      (libsource (lib "eagle-import") (part "RESISTOR0402_RES"))
    )
    (comp (ref "R31")
      (value "100k")
      (footprint "eagle-import:0402_RES")
      (description "RES SMD 100K OHM 1% 1/16W 0402")
      (fields (field (name "MANUFACTURER") "Yageo") (field (name "MPN") "RC0402FR-07100KL"))
      (libsource (lib "eagle-import") (part "RESISTOR0402_RES"))
    )
    (comp (ref "R34")
      (value "953k")
      (footprint "eagle-import:0805_RES")
      (description "RES SMD 953K OHM 0.1% 1/8W 0805")
      (fields
        (field (name "MANUFACTURER") "Panasonic Electronic Components")
        (field (name "MPN") "ERA-6AEB9533V")
      )
      (libsource (lib "eagle-import") (part "RESISTOR0805_RES"))
    )
    (comp (ref "R35")
      (value "953k")
      (footprint "eagle-import:0805_RES")
      (description "RES SMD 953K OHM 0.1% 1/8W 0805")
      (fields
        (field (name "MANUFACTURER") "Panasonic Electronic Components")
        (field (name "MPN") "ERA-6AEB9533V")
      )
      (libsource (lib "eagle-import") (part "RESISTOR0805_RES"))
    )
    (comp (ref "R36")
      (value "953k")
      (footprint "eagle-import:0805_RES")
      (description "RES SMD 953K OHM 0.1% 1/8W 0805")
      (fields
        (field (name "MANUFACTURER") "Panasonic Electronic Components")
        (field (name "MPN") "ERA-6AEB9533V")
      )
      (libsource (lib "eagle-import") (part "RESISTOR0805_RES"))
    )
    (comp (ref "R37")
      (value "953k")
      (footprint "eagle-import:0805_RES")
      (description "RES SMD 953K OHM 0.1% 1/8W 0805")
      (fields
        (field (name "MANUFACTURER") "Panasonic Electronic Components")
        (field (name "MPN") "ERA-6AEB9533V")
      )
      (libsource (lib "eagle-import") (part "RESISTOR0805_RES"))
    )
    (comp (ref "R38")
      (value "953k")
      (footprint "eagle-import:0805_RES")
      (description "RES SMD 953K OHM 0.1% 1/8W 0805")
      (fields
        (field (name "MANUFACTURER") "Panasonic Electronic Components")
        (field (name "MPN") "ERA-6AEB9533V")
      )
      (libsource (lib "eagle-import") (part "RESISTOR0805_RES"))
    )
    (comp (ref "R39")
      (value "953k")
      (footprint "eagle-import:0805_RES")
      (description "RES SMD 953K OHM 0.1% 1/8W 0805")
      (fields
        (field (name "MANUFACTURER") "Panasonic Electronic Components")
        (field (name "MPN") "ERA-6AEB9533V")
      )
      (libsource (lib "eagle-import") (part "RESISTOR0805_RES"))
    )
    (comp (ref "R40")
      (value "953k")
      (footprint "eagle-import:0805_RES")
      (description "RES SMD 953K OHM 0.1% 1/8W 0805")
      (fields
        (field (name "MANUFACTURER") "Panasonic Electronic Components")
        (field (name "MPN") "ERA-6AEB9533V")
      )
      (libsource (lib "eagle-import") (part "RESISTOR0805_RES"))
    )
    (comp (ref "R41")
      (value "953k")
      (footprint "eagle-import:0805_RES")
      (description "RES SMD 953K OHM 0.1% 1/8W 0805")
      (fields
        (field (name "MANUFACTURER") "Panasonic Electronic Components")
        (field (name "MPN") "ERA-6AEB9533V")
      )
      (libsource (lib "eagle-import") (part "RESISTOR0805_RES"))
    )
    (comp (ref "TP3")
      (value "TEST_POINT_0.078IN")
      (footprint "eagle-import:TESTPOINT_0.078IN")
      (libsource (lib "eagle-import") (part "TEST_POINT_0.078IN"))
    )
    (comp (ref "TP4")
      (value "TEST_POINT_0.078IN")
      (footprint "eagle-import:TESTPOINT_0.078IN")
      (libsource (lib "eagle-import") (part "TEST_POINT_0.078IN"))
    )
    (comp (ref "U2")
      (value "ADA4096-4ACPZ-R7")
      (footprint "eagle-import:CP_16_27")
      (description "IC OPAMP GP 4 CIRCUIT 16LFCSP")
      (fields
        (field (name "MANUFACTURER_PART_NUMBER") "ADA40964ACPZR7")
        (field (name "DIGIKEY") "ADA4096-4ACPZ-R7CT-ND")
        (field (name "MANUFACTURER") "Analog Devices Inc.")
        (field (name "MPN") "ADA4096-4ACPZ-R7")
      )
      (libsource (lib "eagle-import") (part "ADA4096-4ACPZ-R7"))
    )
    (comp (ref "U6")
      (value "IRM-03-5V")
      (footprint "eagle-import:IRM-03")
      (fields (field (name "MANUFACTURER") "Mean Well USA") (field (name "MPN") "IRM-03-5"))
      (libsource (lib "eagle-import") (part "IRM-03-5V"))
    )
    (comp (ref "U11")
      (value "REF2030AIDDCR")
      (footprint "eagle-import:DDC5")
      (description "IC VREF SERIES 1.5V/3V 5SOT")
      (fields
        (field (name "MANUFACTURER_PART_NUMBER") "REF2033AIDDCR")
        (field (name "DIGIKEY") "296-47351-1-ND")
        (field (name "MANUFACTURER") "Texas Instruments")
        (field (name "MANUFACTURER_PART_NUMBER_1") "REF2030AIDDCR")
        (field (name "MPN") "REF2030AIDDCR")
      )
      (libsource (lib "eagle-import") (part "REF2033AIDDCR"))
    )
    (comp (ref "U14")
      (value "SIP32510")
      (footprint "eagle-import:TSOT23-6")
      (fields (field (name "MANUFACTURER") "Vishay") (field (name "MPN") "SIP32510DT-T1-GE3"))
      (libsource (lib "eagle-import") (part "SIP32510"))
    )
    (comp (ref "V1")
      (value "S14K385")
      (footprint "eagle-import:S14K385")
      (description "VARISTOR 620V 5KA DISC 14MM")
      (fields (field (name "MANUFACTURER") "EPCOS (TDK)") (field (name "MPN") "B72214S2381K101"))
      (libsource (lib "eagle-import") (part "S14K385"))
    )
    (comp (ref "C1")
      (value "4.3pF")
      (footprint "eagle-import:0402_CAP")
      (description "CAP CER 4.3PF 50V C0G/NP0 0402")
      (fields
        (field (name "MANUFACTURER") "Murata Electronics North America")
        (field (name "MPN") "GJM1555C1H4R3CB01D")
      )
      (libsource (lib "eagle-import") (part "CAPACITOR0402_CAP"))
    )
    (comp (ref "C2")
      (value "4.3pF")
      (footprint "eagle-import:0402_CAP")
      (description "CAP CER 4.3PF 50V C0G/NP0 0402")
      (fields
        (field (name "MANUFACTURER") "Murata Electronics North America")
        (field (name "MPN") "GJM1555C1H4R3CB01D")
      )
      (libsource (lib "eagle-import") (part "CAPACITOR0402_CAP"))
    )
    (comp (ref "C14")
      (value "0.1uF")
      (footprint "eagle-import:0402_CAP")
      (description "CAP CER 0.1UF 10V X5R 0402")
      (fields (field (name "MANUFACTURER") "Yageo") (field (name "MPN") "CC0402KRX5R6BB104"))
      (libsource (lib "eagle-import") (part "CAPACITOR0402_CAP"))
    )
    (comp (ref "C15")
      (value "0.1uF")
      (footprint "eagle-import:0402_CAP")
      (description "CAP CER 0.1UF 10V X5R 0402")
      (fields (field (name "MANUFACTURER") "Yageo") (field (name "MPN") "CC0402KRX5R6BB104"))
      (libsource (lib "eagle-import") (part "CAPACITOR0402_CAP"))
    )
    (comp (ref "C16")
      (value "0.1uF")
      (footprint "eagle-import:0402_CAP")
      (description "CAP CER 0.1UF 10V X5R 0402")
      (fields (field (name "MANUFACTURER") "Yageo") (field (name "MPN") "CC0402KRX5R6BB104"))
      (libsource (lib "eagle-import") (part "CAPACITOR0402_CAP"))
    )
    (comp (ref "C19")
      (value "1uF")
      (footprint "eagle-import:0402_CAP")
      (description "CAP CER 1UF 10V X7S 0402")
      (fields
        (field (name "MANUFACTURER") "Murata Electronics North America")
        (field (name "MPN") "GCM155C71A105KE38D")
      )
      (libsource (lib "eagle-import") (part "CAPACITOR0402_CAP"))
    )
    (comp (ref "C20")
      (value "1uF")
      (footprint "eagle-import:0402_CAP")
      (description "CAP CER 1UF 10V X7S 0402")
      (fields
        (field (name "MANUFACTURER") "Murata Electronics North America")
        (field (name "MPN") "GCM155C71A105KE38D")
      )
      (libsource (lib "eagle-import") (part "CAPACITOR0402_CAP"))
    )
    (comp (ref "C21")
      (value "1uF")
      (footprint "eagle-import:0402_CAP")
      (description "CAP CER 1UF 10V X7S 0402")
      (fields
        (field (name "MANUFACTURER") "Murata Electronics North America")
        (field (name "MPN") "GCM155C71A105KE38D")
      )
      (libsource (lib "eagle-import") (part "CAPACITOR0402_CAP"))
    )
    (comp (ref "C24")
      (value "4.7uF")
      (footprint "eagle-import:0402_CAP")
      (description "CAP CER 4.7UF 6.3V X5R 0402")
      (fields (field (name "MANUFACTURER") "TDK Corporation ") (field (name "MPN") "C1005X5R0J475K050BC "))
      (libsource (lib "eagle-import") (part "CAPACITOR0402_CAP"))
    )
    (comp (ref "D5")
      (value "LED0603")
      (footprint "eagle-import:LED-0603")
      (description "LED RED DIFFUSED 1608 SMD")
      (fields
        (field (name "DIGIKEY") "SML-D12U1WT86CT-ND")
        (field (name "MANUFACTURER") "Rohm Semiconductor")
        (field (name "MPN") "SML-D12U1WT86")
      )
      (libsource (lib "eagle-import") (part "LED0603"))
    )
    (comp (ref "J2")
      (value "TC2030-JLINK-L")
      (footprint "eagle-import:TC2030-IDC")
      (fields (field (name "DIGIKEY") "DNP") (field (name "MANUFACTURER") "DNP") (field (name "MPN") "DNP"))
      (libsource (lib "eagle-import") (part "TC2030-JLINK-L"))
    )
    (comp (ref "R9")
      (value "1.69k")
      (footprint "eagle-import:0402_RES")
      (description "RES SMD 1.69K OHM 1% 1/16W 0402")
      (fields (field (name "MANUFACTURER") "Yageo") (field (name "MPN") "RC0402FR-071K69L"))
      (libsource (lib "eagle-import") (part "RESISTOR0402_RES"))
    )
    (comp (ref "R23")
      (value "10k")
      (footprint "eagle-import:0402_RES")
      (description "RES SMD 10K OHM 1% 1/16W 0402")
      (fields
        (field (name "MANUFACTURER") "Stackpole Electronics Inc.  ")
        (field (name "MPN") "RMCF0402FT10K0  ")
      )
      (libsource (lib "eagle-import") (part "RESISTOR0402_RES"))
    )
    (comp (ref "S1")
      (value "B3U-1000P")
      (footprint "eagle-import:B3U-1000P")
      (fields (field (name "MANUFACTURER") "Omron"))
      (libsource (lib "eagle-import") (part "B3U-1000P"))
    )
    (comp (ref "U15")
      (value "STM32L432KC")
      (footprint "eagle-import:UQFN-32")
      (fields (field (name "MANUFACTURER") "STMicroelectronics") (field (name "MPN") "STM32L432KCU6"))
      (libsource (lib "eagle-import") (part "STM32L432KC"))
    )
    (comp (ref "U16")
      (value "TCA9406DCUR")
      (footprint "eagle-import:DCU8")
      (description "IC TRNSLTR BIDIRECTIONAL US8")
      (fields
        (field (name "DIGIKEY") "296-28109-1-ND")
        (field (name "MANUFACTURER") "Texas Instruments")
        (field (name "MPN") "TCA9406DCUR")
      )
      (libsource (lib "eagle-import") (part "TCA9406DCUR"))
    )
    (comp (ref "U17")
      (value "TPS79330DBVR")
      (footprint "eagle-import:DBV5")
      (description "IC REG LINEAR 3V 200MA SOT23-5")
      (fields
        (field (name "DIGIKEY") "296-12159-1-ND")
        (field (name "MANUFACTURER") "Texas Instruments")
        (field (name "MPN") "TPS79330DBVR")
      )
      (libsource (lib "eagle-import") (part "TPS79330DBVR"))
    )
    (comp (ref "X1")
      (value "ABS05-32.768KHZ-T")
      (footprint "eagle-import:ABS05")
      (fields (field (name "MANUFACTURER") "Abracon"))
      (libsource (lib "eagle-import") (part "ABS05-32.768KHZ-T"))
    )
    (comp (ref "C9")
      (value "0.1uF")
      (footprint "eagle-import:0402_CAP")
      (description "CAP CER 0.1UF 10V X5R 0402")
      (fields (field (name "MANUFACTURER") "Yageo") (field (name "MPN") "CC0402KRX5R6BB104"))
      (libsource (lib "eagle-import") (part "CAPACITOR0402_CAP"))
    )
    (comp (ref "C25")
      (value "10uF")
      (footprint "eagle-import:0402_CAP")
      (description "CAP CER 10UF 6.3V X5R 0402")
      (fields
        (field (name "MANUFACTURER") "Murata Electronics North America")
        (field (name "MPN") "GRJ155R60J106ME11D")
      )
      (libsource (lib "eagle-import") (part "CAPACITOR0402_CAP"))
    )
    (comp (ref "R13")
      (value "10k")
      (footprint "eagle-import:0402_RES")
      (description "RES SMD 10K OHM 1% 1/16W 0402")
      (fields
        (field (name "MANUFACTURER") "Stackpole Electronics Inc. ")
        (field (name "MPN") "RMCF0402FT10K0 ")
      )
      (libsource (lib "eagle-import") (part "RESISTOR0402_RES"))
    )
    (comp (ref "R17")
      (value "10k")
      (footprint "eagle-import:0402_RES")
      (description "RES SMD 10K OHM 1% 1/16W 0402")
      (fields
        (field (name "MANUFACTURER") "Stackpole Electronics Inc. ")
        (field (name "MPN") "RMCF0402FT10K0 ")
      )
      (libsource (lib "eagle-import") (part "RESISTOR0402_RES"))
    )
    (comp (ref "U7")
      (value "LIS2DH12")
      (footprint "eagle-import:LGA-12")
      (fields
        (field (name "MANUFACTURER") "STMicroelectronics")
        (field (name "MPN") "LIS2DW12TR")
        (field (name "DIGIKEY") "497-14851-1-ND")
        (field (name "MOUSER") "511-LIS2DH12TR")
        (field (name "MPN_1") "LIS2DH12TR")
      )
      (libsource (lib "eagle-import") (part "LIS2DW12"))
    )
    (comp (ref "B1")
      (value "MS518SE")
      (footprint "eagle-import:MS518SE-FL35E")
      (fields (field (name "MANUFACTURER") "Seiko") (field (name "MPN") "MS518SE-FL35E"))
      (libsource (lib "eagle-import") (part "MS518SE"))
    )
    (comp (ref "C3")
      (value "47pF")
      (footprint "eagle-import:0402_CAP")
      (description "CAP CER 47PF 100V C0G/NP0 0402")
      (fields
        (field (name "MANUFACTURER") "Murata Electronics North America")
        (field (name "MPN") "GRM1555C2A470JA01D")
      )
      (libsource (lib "eagle-import") (part "CAPACITOR0402_CAP"))
    )
    (comp (ref "C17")
      (value "0.82uF")
      (footprint "eagle-import:0402_CAP")
      (description "CAP CER 0.82UF 10V X5R 0402")
      (fields (field (name "MANUFACTURER") "Yageo") (field (name "MPN") "CC0402KRX5R6BB824"))
      (libsource (lib "eagle-import") (part "CAPACITOR0402_CAP"))
    )
    (comp (ref "C18")
      (value "1uF")
      (footprint "eagle-import:0402_CAP")
      (description "CAP CER 1UF 10V X7S 0402")
      (fields
        (field (name "MANUFACTURER") "Murata Electronics North America")
        (field (name "MPN") "GCM155C71A105KE38D")
      )
      (libsource (lib "eagle-import") (part "CAPACITOR0402_CAP"))
    )
    (comp (ref "C22")
      (value "2.2uF")
      (footprint "eagle-import:0402_CAP")
      (fields
        (field (name "MANUFACTURER") "Murata Electronics North America")
        (field (name "MPN") "GRM155C70J225KE11D")
      )
      (libsource (lib "eagle-import") (part "CAPACITOR0402_CAP"))
    )
    (comp (ref "JP1")
      (value "M024UCON-15767")
      (footprint "eagle-import:JST-2-SMD-VERT")
      (description "CONN HEADER PH TOP 2POS 2MM SMD")
      (fields
        (field (name "MANUFACTURER") "JST Sales America Inc.")
        (field (name "MPN") "B2B-PH-SM4-TB(LF)(SN)")
      )
      (libsource (lib "eagle-import") (part "M024UCON-15767"))
    )
    (comp (ref "JP2")
      (value "M024UCON-15767")
      (footprint "eagle-import:JST-2-SMD-VERT")
      (description "CONN HEADER PH TOP 2POS 2MM SMD")
      (fields
        (field (name "MANUFACTURER") "JST Sales America Inc.")
        (field (name "MPN") "B2B-PH-SM4-TB(LF)(SN)")
      )
      (libsource (lib "eagle-import") (part "M024UCON-15767"))
    )
    (comp (ref "Q1")
      (value "MOSFET-NCHANNELSMD")
      (footprint "eagle-import:SOT23-3")
      (description "MOSFET N-CH 60V 115MA SOT23-3")
      (fields
        (field (name "DIGIKEY") "2N7002-FDICT-ND")
        (field (name "MANUFACTURER") "Diodes Incorporated")
        (field (name "MPN") "2N7002-7-F")
      )
      (libsource (lib "eagle-import") (part "MOSFET-NCHANNELSMD"))
    )
    (comp (ref "R18")
      (value "10k")
      (footprint "eagle-import:0402_RES")
      (description "RES SMD 10K OHM 1% 1/16W 0402")
      (fields
        (field (name "MANUFACTURER") "Stackpole Electronics Inc. ")
        (field (name "MPN") "RMCF0402FT10K0 ")
      )
      (libsource (lib "eagle-import") (part "RESISTOR0402_RES"))
    )
    (comp (ref "R19")
      (value "10k")
      (footprint "eagle-import:0402_RES")
      (description "RES SMD 10K OHM 1% 1/16W 0402")
      (fields
        (field (name "MANUFACTURER") "Stackpole Electronics Inc. ")
        (field (name "MPN") "RMCF0402FT10K0 ")
      )
      (libsource (lib "eagle-import") (part "RESISTOR0402_RES"))
    )
    (comp (ref "R20")
      (value "10k")
      (footprint "eagle-import:0402_RES")
      (description "RES SMD 10K OHM 1% 1/16W 0402")
      (fields
        (field (name "MANUFACTURER") "Stackpole Electronics Inc. ")
        (field (name "MPN") "RMCF0402FT10K0 ")
      )
      (libsource (lib "eagle-import") (part "RESISTOR0402_RES"))
    )
    (comp (ref "R21")
      (value "10k")
      (footprint "eagle-import:0402_RES")
      (description "RES SMD 10K OHM 1% 1/16W 0402")
      (fields
        (field (name "MANUFACTURER") "Stackpole Electronics Inc. ")
        (field (name "MPN") "RMCF0402FT10K0 ")
      )
      (libsource (lib "eagle-import") (part "RESISTOR0402_RES"))
    )
    (comp (ref "R22")
      (value "10k")
      (footprint "eagle-import:0402_RES")
      (description "RES SMD 10K OHM 1% 1/16W 0402")
      (fields
        (field (name "MANUFACTURER") "Stackpole Electronics Inc. ")
        (field (name "MPN") "RMCF0402FT10K0 ")
      )
      (libsource (lib "eagle-import") (part "RESISTOR0402_RES"))
    )
    (comp (ref "R29")
      (value "100k")
      (footprint "eagle-import:0402_RES")
      (description "RES SMD 100K OHM 1% 1/16W 0402")
      (fields (field (name "MANUFACTURER") "Yageo") (field (name "MPN") "RC0402FR-07100KL"))
      (libsource (lib "eagle-import") (part "RESISTOR0402_RES"))
    )
    (comp (ref "R30")
      (value "100k")
      (footprint "eagle-import:0402_RES")
      (description "RES SMD 100K OHM 1% 1/16W 0402")
      (fields (field (name "MANUFACTURER") "Yageo") (field (name "MPN") "RC0402FR-07100KL"))
      (libsource (lib "eagle-import") (part "RESISTOR0402_RES"))
    )
    (comp (ref "R33")
      (value "825k")
      (footprint "eagle-import:0402_RES")
      (description "RES SMD 825K OHM 1% 1/10W 0402")
      (fields
        (field (name "MANUFACTURER") "Panasonic Electronic Components")
        (field (name "MPN") "ERJ-2RKF8253X")
      )
      (libsource (lib "eagle-import") (part "RESISTOR0402_RES"))
    )
    (comp (ref "R42")
      (value "1M")
      (footprint "eagle-import:0402_RES")
      (description "RES 1M OHM 1% 1/16W 0402")
      (fields
        (field (name "MANUFACTURER") "Stackpole Electronics Inc ")
        (field (name "MPN") "RMCF0402FT1M00 ")
      )
      (libsource (lib "eagle-import") (part "RESISTOR0402_RES"))
    )
    (comp (ref "R43")
      (value "1M")
      (footprint "eagle-import:0402_RES")
      (description "RES 1M OHM 1% 1/16W 0402")
      (fields
        (field (name "MANUFACTURER") "Stackpole Electronics Inc ")
        (field (name "MPN") "RMCF0402FT1M00 ")
      )
      (libsource (lib "eagle-import") (part "RESISTOR0402_RES"))
    )
    (comp (ref "R44")
      (value "1M")
      (footprint "eagle-import:0402_RES")
      (description "RES 1M OHM 1% 1/16W 0402")
      (fields
        (field (name "MANUFACTURER") "Stackpole Electronics Inc ")
        (field (name "MPN") "RMCF0402FT1M00 ")
      )
      (libsource (lib "eagle-import") (part "RESISTOR0402_RES"))
    )
    (comp (ref "U1")
      (value "AB1815-T3")
      (footprint "eagle-import:QFN-16-3MM")
      (fields (field (name "MANUFACTURER") "Abracon"))
      (libsource (lib "eagle-import") (part "AB1815-T3"))
    )
    (comp (ref "U9")
      (value "MAX67XXMAX6749MAX67XX")
      (footprint "eagle-import:SOT-23-8")
      (fields (field (name "MANUFACTURER") "Maxim Integrated") (field (name "MPN") "MAX6749KA+T"))
      (libsource (lib "eagle-import") (part "MAX67XXMAX67XXMAX6749"))
    )
    (comp (ref "X2")
      (value "ABS07-32.768KHZ-7-T")
      (footprint "eagle-import:2-SMD")
      (fields (field (name "MANUFACTURER") "ABRACON") (field (name "MPN") "ABS07-32.768KHZ-7-T "))
      (libsource (lib "eagle-import") (part "ABS07-32.768KHZ-7-T"))
    )
  )
  (nets
    (net (code "1") (name "5V") (class "Default")
      (node (ref "ASSY1") (pin "VIN") (pinfunction "VIN_VIN") (pintype "power_in"))
      (node (ref "C27") (pin "1") (pinfunction "1_1") (pintype "bidirectional"))
      (node (ref "C28") (pin "1") (pinfunction "1_1") (pintype "bidirectional"))
      (node (ref "C29") (pin "+") (pinfunction "+_+") (pintype "passive"))
      (node (ref "R24") (pin "1") (pinfunction "1_1") (pintype "passive"))
      (node (ref "R29") (pin "1") (pinfunction "1_1") (pintype "passive"))
      (node (ref "R43") (pin "1") (pinfunction "1_1") (pintype "passive"))
      (node (ref "U6") (pin "V+") (pinfunction "V+_V+") (pintype "bidirectional"))
    )
    (net (code "2") (name "ACCEL_INT") (class "Default")
      (node (ref "ASSY1") (pin "C4") (pinfunction "C4_C4") (pintype "bidirectional"))
      (node (ref "U7") (pin "12") (pinfunction "INT1_12") (pintype "bidirectional"))
    )
    (net (code "3") (name "AC_COPROC_VCC") (class "Default")
      (node (ref "C15") (pin "1") (pinfunction "1_1") (pintype "bidirectional"))
      (node (ref "C16") (pin "1") (pinfunction "1_1") (pintype "bidirectional"))
      (node (ref "C20") (pin "1") (pinfunction "1_1") (pintype "bidirectional"))
      (node (ref "C21") (pin "1") (pinfunction "1_1") (pintype "bidirectional"))
      (node (ref "C24") (pin "1") (pinfunction "1_1") (pintype "bidirectional"))
      (node (ref "J2") (pin "1") (pinfunction "VCC_1") (pintype "bidirectional"))
      (node (ref "R9") (pin "2") (pinfunction "2_2") (pintype "passive"))
      (node (ref "U15") (pin "1") (pinfunction "VDD_1") (pintype "bidirectional"))
      (node (ref "U15") (pin "17") (pinfunction "VDD_17") (pintype "bidirectional"))
      (node (ref "U16") (pin "3") (pinfunction "VCCA_3") (pintype "power_in"))
      (node (ref "U16") (pin "6") (pinfunction "OE_6") (pintype "input"))
      (node (ref "U17") (pin "5") (pinfunction "OUT_5") (pintype "output"))
    )
    (net (code "4") (name "AC_L_800V_DETECT") (class "Default")
      (node (ref "ASSY1") (pin "B1") (pinfunction "B1_B1") (pintype "bidirectional"))
      (node (ref "C6") (pin "1") (pinfunction "1_1") (pintype "bidirectional"))
      (node (ref "D1") (pin "C") (pinfunction "C_C") (pintype "passive"))
      (node (ref "D6") (pin "A") (pinfunction "A_A") (pintype "passive"))
      (node (ref "U15") (pin "27") (pinfunction "PB4/~{JTRST}_27") (pintype "bidirectional"))
    )
    (net (code "5") (name "AC_L_HV_OUT") (class "Default")
      (node (ref "ASSY1") (pin "A0") (pinfunction "A0_A0") (pintype "bidirectional"))
      (node (ref "R6") (pin "2") (pinfunction "2_2") (pintype "passive"))
      (node (ref "U15") (pin "6") (pinfunction "PA0/CLKIN_6") (pintype "bidirectional"))
      (node (ref "U2") (pin "14") (pinfunction "OUT_14") (pintype "bidirectional"))
    )
    (net (code "6") (name "AC_L_LV_OUT") (class "Default")
      (node (ref "ASSY1") (pin "B3") (pinfunction "B3_B3") (pintype "bidirectional"))
      (node (ref "R10") (pin "2") (pinfunction "2_2") (pintype "passive"))
      (node (ref "U15") (pin "9") (pinfunction "PA3_9") (pintype "bidirectional"))
      (node (ref "U2") (pin "7") (pinfunction "OUT_7") (pintype "bidirectional"))
    )
    (net (code "7") (name "AC_L_SENSE") (class "Default")
      (node (ref "D14") (pin "A") (pinfunction "A_A") (pintype "passive"))
      (node (ref "F1") (pin "P$2") (pinfunction "P$2_P$2") (pintype "bidirectional"))
      (node (ref "R1") (pin "1") (pinfunction "1_1") (pintype "passive"))
      (node (ref "R34") (pin "1") (pinfunction "1_1") (pintype "passive"))
      (node (ref "R39") (pin "2") (pinfunction "2_2") (pintype "passive"))
    )
    (net (code "8") (name "AC_N") (class "Default")
      (node (ref "D15") (pin "A") (pinfunction "A_A") (pintype "passive"))
      (node (ref "R36") (pin "1") (pinfunction "1_1") (pintype "passive"))
      (node (ref "R40") (pin "2") (pinfunction "2_2") (pintype "passive"))
      (node (ref "TP4") (pin "1") (pinfunction "TESTPOINT_1") (pintype "bidirectional"))
      (node (ref "U6") (pin "AC/N") (pinfunction "AC/N_AC/N") (pintype "bidirectional"))
      (node (ref "V1") (pin "2") (pinfunction "2_2") (pintype "passive"))
    )
    (net (code "9") (name "AC_N_800V_DETECT") (class "Default")
      (node (ref "ASSY1") (pin "A1") (pinfunction "A1_A1") (pintype "bidirectional"))
      (node (ref "C7") (pin "1") (pinfunction "1_1") (pintype "bidirectional"))
      (node (ref "D10") (pin "A") (pinfunction "A_A") (pintype "passive"))
      (node (ref "D2") (pin "C") (pinfunction "C_C") (pintype "passive"))
      (node (ref "U15") (pin "28") (pinfunction "PB5_28") (pintype "bidirectional"))
    )
    (net (code "10") (name "AC_N_HV_OUT") (class "Default")
      (node (ref "ASSY1") (pin "B4") (pinfunction "B4_B4") (pintype "bidirectional"))
      (node (ref "R7") (pin "2") (pinfunction "2_2") (pintype "passive"))
      (node (ref "U15") (pin "10") (pinfunction "PA4_10") (pintype "bidirectional"))
      (node (ref "U2") (pin "6") (pinfunction "OUT_6") (pintype "bidirectional"))
    )
    (net (code "11") (name "AC_N_LV_OUT") (class "Default")
      (node (ref "ASSY1") (pin "B5") (pinfunction "B5_B5") (pintype "bidirectional"))
      (node (ref "R11") (pin "1") (pinfunction "1_1") (pintype "passive"))
      (node (ref "U15") (pin "7") (pinfunction "PA1_7") (pintype "bidirectional"))
      (node (ref "U2") (pin "15") (pinfunction "OUT_15") (pintype "bidirectional"))
    )
    (net (code "12") (name "AC_SCL") (class "Default")
      (node (ref "U15") (pin "19") (pinfunction "PA9_19") (pintype "bidirectional"))
      (node (ref "U16") (pin "5") (pinfunction "SCL_A_5") (pintype "bidirectional"))
    )
    (net (code "13") (name "AC_SDA") (class "Default")
      (node (ref "U15") (pin "20") (pinfunction "PA10_20") (pintype "bidirectional"))
      (node (ref "U16") (pin "4") (pinfunction "SDA_A_4") (pintype "bidirectional"))
    )
    (net (code "14") (name "AC_SENSE_PWR_EN") (class "Default")
      (node (ref "ASSY1") (pin "C3") (pinfunction "C3_C3") (pintype "bidirectional"))
      (node (ref "R31") (pin "2") (pinfunction "2_2") (pintype "passive"))
      (node (ref "U14") (pin "3") (pinfunction "EN_3") (pintype "bidirectional"))
    )
    (net (code "15") (name "AC_SENSE_VCC") (class "Default")
      (node (ref "U11") (pin "3") (pinfunction "EN_3") (pintype "input"))
      (node (ref "U11") (pin "4") (pinfunction "VIN_4") (pintype "input"))
      (node (ref "U14") (pin "1") (pinfunction "VLOAD_1") (pintype "bidirectional"))
      (node (ref "U14") (pin "2") (pinfunction "VLOAD_2") (pintype "bidirectional"))
      (node (ref "U17") (pin "1") (pinfunction "IN_1") (pintype "input"))
      (node (ref "U17") (pin "3") (pinfunction "EN_3") (pintype "passive"))
    )
    (net (code "16") (name "ANT") (class "Default")
      (node (ref "A1") (pin "0") (pinfunction "1_0") (pintype "output"))
      (node (ref "L1") (pin "2") (pinfunction "2_2") (pintype "bidirectional"))
    )
    (net (code "17") (name "BOOT0") (class "Default")
      (node (ref "R23") (pin "2") (pinfunction "2_2") (pintype "passive"))
      (node (ref "U15") (pin "31") (pinfunction "PH3/BOOT0_31") (pintype "bidirectional"))
    )
    (net (code "18") (name "DO_NOT_CONNECT") (class "Default")
      (node (ref "ASSY1") (pin "D7") (pinfunction "D7_D7") (pintype "bidirectional"))
    )
    (net (code "19") (name "GND") (class "Default")
      (node (ref "A1") (pin "1") (pinfunction "2_1") (pintype "power_in"))
      (node (ref "A1") (pin "2") (pinfunction "2_2") (pintype "power_in"))
      (node (ref "A1") (pin "3") (pinfunction "2_3") (pintype "power_in"))
      (node (ref "A1") (pin "4") (pinfunction "2_4") (pintype "power_in"))
      (node (ref "ASSY1") (pin "GND") (pinfunction "GND_GND") (pintype "power_in"))
      (node (ref "ASSY1") (pin "GND@2") (pinfunction "GND_GND@2") (pintype "power_in"))
      (node (ref "B1") (pin "-") (pinfunction "-_-") (pintype "bidirectional"))
      (node (ref "C1") (pin "1") (pinfunction "1_1") (pintype "bidirectional"))
      (node (ref "C10") (pin "2") (pinfunction "2_2") (pintype "bidirectional"))
      (node (ref "C11") (pin "2") (pinfunction "2_2") (pintype "bidirectional"))
      (node (ref "C12") (pin "2") (pinfunction "2_2") (pintype "bidirectional"))
      (node (ref "C13") (pin "2") (pinfunction "2_2") (pintype "bidirectional"))
      (node (ref "C14") (pin "2") (pinfunction "2_2") (pintype "bidirectional"))
      (node (ref "C15") (pin "2") (pinfunction "2_2") (pintype "bidirectional"))
      (node (ref "C16") (pin "2") (pinfunction "2_2") (pintype "bidirectional"))
      (node (ref "C17") (pin "2") (pinfunction "2_2") (pintype "bidirectional"))
      (node (ref "C18") (pin "2") (pinfunction "2_2") (pintype "bidirectional"))
      (node (ref "C19") (pin "2") (pinfunction "2_2") (pintype "bidirectional"))
      (node (ref "C2") (pin "1") (pinfunction "1_1") (pintype "bidirectional"))
      (node (ref "C20") (pin "2") (pinfunction "2_2") (pintype "bidirectional"))
      (node (ref "C21") (pin "2") (pinfunction "2_2") (pintype "bidirectional"))
      (node (ref "C22") (pin "2") (pinfunction "2_2") (pintype "bidirectional"))
      (node (ref "C23") (pin "2") (pinfunction "2_2") (pintype "bidirectional"))
      (node (ref "C24") (pin "2") (pinfunction "2_2") (pintype "bidirectional"))
      (node (ref "C25") (pin "2") (pinfunction "2_2") (pintype "bidirectional"))
      (node (ref "C26") (pin "1") (pinfunction "1_1") (pintype "bidirectional"))
      (node (ref "C27") (pin "2") (pinfunction "2_2") (pintype "bidirectional"))
      (node (ref "C28") (pin "2") (pinfunction "2_2") (pintype "bidirectional"))
      (node (ref "C29") (pin "-") (pinfunction "-_-") (pintype "passive"))
      (node (ref "C3") (pin "2") (pinfunction "2_2") (pintype "bidirectional"))
      (node (ref "C4") (pin "1") (pinfunction "1_1") (pintype "bidirectional"))
      (node (ref "C5") (pin "1") (pinfunction "1_1") (pintype "bidirectional"))
      (node (ref "C6") (pin "2") (pinfunction "2_2") (pintype "bidirectional"))
      (node (ref "C7") (pin "2") (pinfunction "2_2") (pintype "bidirectional"))
      (node (ref "C8") (pin "1") (pinfunction "1_1") (pintype "bidirectional"))
      (node (ref "C9") (pin "2") (pinfunction "2_2") (pintype "bidirectional"))
      (node (ref "D1") (pin "A") (pinfunction "A_A") (pintype "passive"))
      (node (ref "D2") (pin "A") (pinfunction "A_A") (pintype "passive"))
      (node (ref "J1") (pin "6") (pinfunction "GND_6") (pintype "bidirectional"))
      (node (ref "J1") (pin "B") (pinfunction "B_B") (pintype "bidirectional"))
      (node (ref "J1") (pin "MOUNT0") (pinfunction "GND_MOUNT0") (pintype "bidirectional"))
      (node (ref "J1") (pin "MOUNT1") (pinfunction "GND_MOUNT1") (pintype "bidirectional"))
      (node (ref "J1") (pin "MOUNT2") (pinfunction "GND_MOUNT2") (pintype "bidirectional"))
      (node (ref "J1") (pin "MOUNT3") (pinfunction "GND_MOUNT3") (pintype "bidirectional"))
      (node (ref "J2") (pin "5") (pinfunction "GND_5") (pintype "bidirectional"))
      (node (ref "JP1") (pin "GND") (pinfunction "1_GND") (pintype "passive"))
      (node (ref "JP2") (pin "GND") (pinfunction "1_GND") (pintype "passive"))
      (node (ref "Q1") (pin "2") (pinfunction "S_2") (pintype "passive"))
      (node (ref "R18") (pin "2") (pinfunction "2_2") (pintype "passive"))
      (node (ref "R23") (pin "1") (pinfunction "1_1") (pintype "passive"))
      (node (ref "R25") (pin "2") (pinfunction "2_2") (pintype "passive"))
      (node (ref "R27") (pin "1") (pinfunction "1_1") (pintype "passive"))
      (node (ref "R28") (pin "1") (pinfunction "1_1") (pintype "passive"))
      (node (ref "R30") (pin "2") (pinfunction "2_2") (pintype "passive"))
      (node (ref "R31") (pin "1") (pinfunction "1_1") (pintype "passive"))
      (node (ref "R35") (pin "1") (pinfunction "1_1") (pintype "passive"))
      (node (ref "R37") (pin "1") (pinfunction "1_1") (pintype "passive"))
      (node (ref "R38") (pin "2") (pinfunction "2_2") (pintype "passive"))
      (node (ref "R41") (pin "2") (pinfunction "2_2") (pintype "passive"))
      (node (ref "R42") (pin "2") (pinfunction "2_2") (pintype "passive"))
      (node (ref "R44") (pin "2") (pinfunction "2_2") (pintype "passive"))
      (node (ref "S1") (pin "1") (pinfunction "P$1_1") (pintype "passive"))
      (node (ref "U1") (pin "3") (pinfunction "~{EXTR}_3") (pintype "bidirectional"))
      (node (ref "U1") (pin "GND") (pinfunction "VSS_GND") (pintype "bidirectional"))
      (node (ref "U10") (pin "17") (pinfunction "EPAD_17") (pintype "power_in"))
      (node (ref "U10") (pin "6") (pinfunction "GND_6") (pintype "power_in"))
      (node (ref "U11") (pin "2") (pinfunction "GND_2") (pintype "power_in"))
      (node (ref "U12") (pin "4") (pinfunction "GND_4") (pintype "bidirectional"))
      (node (ref "U13") (pin "4") (pinfunction "GND_4") (pintype "bidirectional"))
      (node (ref "U14") (pin "4") (pinfunction "GND_4") (pintype "bidirectional"))
      (node (ref "U15") (pin "16") (pinfunction "VSS_16") (pintype "bidirectional"))
      (node (ref "U15") (pin "32") (pinfunction "VSS_32") (pintype "bidirectional"))
      (node (ref "U15") (pin "THERMAL") (pinfunction "VSS_THERMAL") (pintype "bidirectional"))
      (node (ref "U16") (pin "2") (pinfunction "GND_2") (pintype "power_in"))
      (node (ref "U17") (pin "2") (pinfunction "GND_2") (pintype "power_in"))
      (node (ref "U2") (pin "10") (pinfunction "V-_10") (pintype "bidirectional"))
      (node (ref "U2") (pin "17") (pinfunction "V-_17") (pintype "bidirectional"))
      (node (ref "U3") (pin "1") (pinfunction "GND_1") (pintype "power_in"))
      (node (ref "U3") (pin "4") (pinfunction "GND_4") (pintype "power_in"))
      (node (ref "U4") (pin "1") (pinfunction "GND_1") (pintype "power_in"))
      (node (ref "U5") (pin "2") (pinfunction "GND_2") (pintype "power_in"))
      (node (ref "U5") (pin "3") (pinfunction "GND_3") (pintype "power_in"))
      (node (ref "U5") (pin "5") (pinfunction "GND_5") (pintype "power_in"))
      (node (ref "U6") (pin "V-") (pinfunction "V-_V-") (pintype "bidirectional"))
      (node (ref "U7") (pin "3") (pinfunction "MISO/SA0_3") (pintype "bidirectional"))
      (node (ref "U7") (pin "5") (pinfunction "GND_5") (pintype "bidirectional"))
      (node (ref "U7") (pin "6") (pinfunction "GND_6") (pintype "bidirectional"))
      (node (ref "U7") (pin "7") (pinfunction "GND_7") (pintype "bidirectional"))
      (node (ref "U7") (pin "8") (pinfunction "GND_8") (pintype "bidirectional"))
      (node (ref "U8") (pin "1") (pinfunction "GND_1") (pintype "bidirectional"))
      (node (ref "U8") (pin "10") (pinfunction "GND_10") (pintype "bidirectional"))
      (node (ref "U8") (pin "12") (pinfunction "GND_12") (pintype "bidirectional"))
      (node (ref "U9") (pin "4") (pinfunction "GND_4") (pintype "bidirectional"))
    )
    (net (code "20") (name "GPS_PPS") (class "Default")
      (node (ref "ASSY1") (pin "D4") (pinfunction "D4_D4") (pintype "bidirectional"))
      (node (ref "U15") (pin "26") (pinfunction "PB3/JTDO/SWO_26") (pintype "bidirectional"))
      (node (ref "U8") (pin "4") (pinfunction "TIMEPULSE_4") (pintype "bidirectional"))
    )
    (net (code "21") (name "GPS_PWR_EN") (class "Default")
      (node (ref "ASSY1") (pin "B2") (pinfunction "B2_B2") (pintype "bidirectional"))
      (node (ref "R28") (pin "2") (pinfunction "2_2") (pintype "passive"))
      (node (ref "U12") (pin "3") (pinfunction "EN_3") (pintype "bidirectional"))
    )
    (net (code "22") (name "GPS_RXD") (class "Default")
      (node (ref "ASSY1") (pin "TX") (pinfunction "TX_TX") (pintype "bidirectional"))
      (node (ref "L3") (pin "2") (pinfunction "P$2_2") (pintype "bidirectional"))
    )
    (net (code "23") (name "GPS_TXD") (class "Default")
      (node (ref "ASSY1") (pin "RX") (pinfunction "RX_RX") (pintype "bidirectional"))
      (node (ref "L2") (pin "2") (pinfunction "P$2_2") (pintype "bidirectional"))
    )
    (net (code "24") (name "GPS_VCC") (class "Default")
      (node (ref "C26") (pin "2") (pinfunction "2_2") (pintype "bidirectional"))
      (node (ref "C5") (pin "2") (pinfunction "2_2") (pintype "bidirectional"))
      (node (ref "C8") (pin "2") (pinfunction "2_2") (pintype "bidirectional"))
      (node (ref "U12") (pin "1") (pinfunction "VLOAD_1") (pintype "bidirectional"))
      (node (ref "U12") (pin "2") (pinfunction "VLOAD_2") (pintype "bidirectional"))
      (node (ref "U8") (pin "6") (pinfunction "V_BCKP_6") (pintype "bidirectional"))
      (node (ref "U8") (pin "7") (pinfunction "VCC_IO_7") (pintype "bidirectional"))
      (node (ref "U8") (pin "8") (pinfunction "VCC_8") (pintype "bidirectional"))
    )
    (net (code "25") (name "Net-(D5-ANODE)") (class "Default")
      (node (ref "D5") (pin "A") (pinfunction "ANODE_A") (pintype "bidirectional"))
      (node (ref "R9") (pin "1") (pinfunction "1_1") (pintype "passive"))
    )
    (net (code "26") (name "Net-(D5-CATHODE)") (class "Default")
      (node (ref "D5") (pin "C") (pinfunction "CATHODE_C") (pintype "bidirectional"))
      (node (ref "U15") (pin "15") (pinfunction "PB1_15") (pintype "bidirectional"))
    )
    (net (code "27") (name "Net-(D6-PadC)") (class "Default")
      (node (ref "D6") (pin "C") (pinfunction "C_C") (pintype "passive"))
      (node (ref "D7") (pin "A") (pinfunction "A_A") (pintype "passive"))
    )
    (net (code "28") (name "Net-(D7-PadC)") (class "Default")
      (node (ref "D7") (pin "C") (pinfunction "C_C") (pintype "passive"))
      (node (ref "D8") (pin "A") (pinfunction "A_A") (pintype "passive"))
    )
    (net (code "29") (name "Net-(D8-PadC)") (class "Default")
      (node (ref "D8") (pin "C") (pinfunction "C_C") (pintype "passive"))
      (node (ref "D9") (pin "A") (pinfunction "A_A") (pintype "passive"))
    )
    (net (code "30") (name "Net-(D9-PadC)") (class "Default")
      (node (ref "D9") (pin "C") (pinfunction "C_C") (pintype "passive"))
      (node (ref "R2") (pin "1") (pinfunction "1_1") (pintype "passive"))
    )
    (net (code "31") (name "Net-(D10-PadC)") (class "Default")
      (node (ref "D10") (pin "C") (pinfunction "C_C") (pintype "passive"))
      (node (ref "D11") (pin "A") (pinfunction "A_A") (pintype "passive"))
    )
    (net (code "32") (name "Net-(D11-PadC)") (class "Default")
      (node (ref "D11") (pin "C") (pinfunction "C_C") (pintype "passive"))
      (node (ref "D12") (pin "A") (pinfunction "A_A") (pintype "passive"))
    )
    (net (code "33") (name "Net-(D12-PadC)") (class "Default")
      (node (ref "D12") (pin "C") (pinfunction "C_C") (pintype "passive"))
      (node (ref "D13") (pin "A") (pinfunction "A_A") (pintype "passive"))
    )
    (net (code "34") (name "Net-(D13-PadC)") (class "Default")
      (node (ref "D13") (pin "C") (pinfunction "C_C") (pintype "passive"))
      (node (ref "R3") (pin "1") (pinfunction "1_1") (pintype "passive"))
    )
    (net (code "35") (name "Net-(D14-PadC)") (class "Default")
      (node (ref "D14") (pin "C") (pinfunction "C_C") (pintype "passive"))
      (node (ref "R2") (pin "2") (pinfunction "2_2") (pintype "passive"))
    )
    (net (code "36") (name "Net-(D15-PadC)") (class "Default")
      (node (ref "D15") (pin "C") (pinfunction "C_C") (pintype "passive"))
      (node (ref "R3") (pin "2") (pinfunction "2_2") (pintype "passive"))
    )
    (net (code "37") (name "Net-(D29-B)") (class "Default")
      (node (ref "D29") (pin "3") (pinfunction "B_3") (pintype "output"))
      (node (ref "R4") (pin "1") (pinfunction "1_1") (pintype "passive"))
    )
    (net (code "38") (name "Net-(D29-G)") (class "Default")
      (node (ref "D29") (pin "4") (pinfunction "G_4") (pintype "output"))
      (node (ref "R5") (pin "1") (pinfunction "1_1") (pintype "passive"))
    )
    (net (code "39") (name "Net-(D29-R)") (class "Default")
      (node (ref "D29") (pin "2") (pinfunction "R_2") (pintype "output"))
      (node (ref "R8") (pin "1") (pinfunction "1_1") (pintype "passive"))
    )
    (net (code "40") (name "Net-(J1-VCC)") (class "Default")
      (node (ref "C23") (pin "1") (pinfunction "1_1") (pintype "bidirectional"))
      (node (ref "J1") (pin "4") (pinfunction "VCC_4") (pintype "bidirectional"))
      (node (ref "R14") (pin "2") (pinfunction "2_2") (pintype "passive"))
      (node (ref "R15") (pin "2") (pinfunction "2_2") (pintype "passive"))
      (node (ref "R16") (pin "2") (pinfunction "2_2") (pintype "passive"))
      (node (ref "R26") (pin "2") (pinfunction "2_2") (pintype "passive"))
      (node (ref "U13") (pin "1") (pinfunction "VLOAD_1") (pintype "bidirectional"))
      (node (ref "U13") (pin "2") (pinfunction "VLOAD_2") (pintype "bidirectional"))
    )
    (net (code "41") (name "Net-(JP1-2)") (class "Default")
      (node (ref "JP1") (pin "VCC") (pinfunction "2_VCC") (pintype "passive"))
      (node (ref "JP2") (pin "VCC") (pinfunction "2_VCC") (pintype "passive"))
      (node (ref "R21") (pin "1") (pinfunction "1_1") (pintype "passive"))
      (node (ref "R33") (pin "1") (pinfunction "1_1") (pintype "passive"))
      (node (ref "U9") (pin "5") (pinfunction "WDS_5") (pintype "bidirectional"))
      (node (ref "U9") (pin "8") (pinfunction "VCC_8") (pintype "bidirectional"))
    )
    (net (code "42") (name "Net-(L2-P$1)") (class "Default")
      (node (ref "L2") (pin "1") (pinfunction "P$1_1") (pintype "bidirectional"))
      (node (ref "U8") (pin "2") (pinfunction "TXD_2") (pintype "bidirectional"))
    )
    (net (code "43") (name "Net-(L3-P$1)") (class "Default")
      (node (ref "L3") (pin "1") (pinfunction "P$1_1") (pintype "bidirectional"))
      (node (ref "U8") (pin "3") (pinfunction "RXD_3") (pintype "bidirectional"))
    )
    (net (code "44") (name "Net-(Q1-D)") (class "Default")
      (node (ref "Q1") (pin "3") (pinfunction "D_3") (pintype "passive"))
      (node (ref "R33") (pin "2") (pinfunction "2_2") (pintype "passive"))
      (node (ref "R42") (pin "1") (pinfunction "1_1") (pintype "passive"))
      (node (ref "R43") (pin "2") (pinfunction "2_2") (pintype "passive"))
      (node (ref "U9") (pin "1") (pinfunction "~{MR}_1") (pintype "bidirectional"))
    )
    (net (code "45") (name "Net-(Q2-D)") (class "Default")
      (node (ref "ASSY1") (pin "WKP") (pinfunction "WKP_WKP") (pintype "bidirectional"))
      (node (ref "Q2") (pin "3") (pinfunction "D_3") (pintype "passive"))
      (node (ref "R24") (pin "2") (pinfunction "2_2") (pintype "passive"))
      (node (ref "R25") (pin "1") (pinfunction "1_1") (pintype "passive"))
    )
    (net (code "46") (name "Net-(R1-Pad2)") (class "Default")
      (node (ref "R1") (pin "2") (pinfunction "2_2") (pintype "passive"))
      (node (ref "U6") (pin "AC/L") (pinfunction "AC/L_AC/L") (pintype "bidirectional"))
      (node (ref "V1") (pin "1") (pinfunction "1_1") (pintype "passive"))
    )
    (net (code "47") (name "Net-(TP3-TESTPOINT)") (class "Default")
      (node (ref "F1") (pin "P$1") (pinfunction "P$1_P$1") (pintype "bidirectional"))
      (node (ref "TP3") (pin "1") (pinfunction "TESTPOINT_1") (pintype "bidirectional"))
    )
    (net (code "48") (name "Net-(U1-AF)") (class "Default")
      (node (ref "C3") (pin "1") (pinfunction "1_1") (pintype "bidirectional"))
      (node (ref "U1") (pin "14") (pinfunction "AF_14") (pintype "bidirectional"))
    )
    (net (code "49") (name "Net-(U1-EXTI)") (class "Default")
      (node (ref "R29") (pin "2") (pinfunction "2_2") (pintype "passive"))
      (node (ref "R30") (pin "1") (pinfunction "1_1") (pintype "passive"))
      (node (ref "U1") (pin "10") (pinfunction "EXTI_10") (pintype "bidirectional"))
    )
    (net (code "50") (name "Net-(U1-VBAT)") (class "Default")
      (node (ref "B1") (pin "+") (pinfunction "+_+") (pintype "bidirectional"))
      (node (ref "R22") (pin "1") (pinfunction "1_1") (pintype "passive"))
      (node (ref "U1") (pin "5") (pinfunction "VBAT_5") (pintype "bidirectional"))
    )
    (net (code "51") (name "Net-(U1-XI)") (class "Default")
      (node (ref "U1") (pin "16") (pinfunction "XI_16") (pintype "bidirectional"))
      (node (ref "X2") (pin "1") (pinfunction "1_1") (pintype "bidirectional"))
    )
    (net (code "52") (name "Net-(U1-XO)") (class "Default")
      (node (ref "U1") (pin "15") (pinfunction "XO_15") (pintype "bidirectional"))
      (node (ref "X2") (pin "2") (pinfunction "2_2") (pintype "bidirectional"))
    )
    (net (code "53") (name "Net-(U2A--)") (class "Default")
      (node (ref "R11") (pin "2") (pinfunction "2_2") (pintype "passive"))
      (node (ref "R36") (pin "2") (pinfunction "2_2") (pintype "passive"))
      (node (ref "R37") (pin "2") (pinfunction "2_2") (pintype "passive"))
      (node (ref "U2") (pin "1") (pinfunction "-_1") (pintype "bidirectional"))
    )
    (net (code "54") (name "Net-(U2B--)") (class "Default")
      (node (ref "R40") (pin "1") (pinfunction "1_1") (pintype "passive"))
      (node (ref "R41") (pin "1") (pinfunction "1_1") (pintype "passive"))
      (node (ref "R7") (pin "1") (pinfunction "1_1") (pintype "passive"))
      (node (ref "U2") (pin "5") (pinfunction "-_5") (pintype "bidirectional"))
    )
    (net (code "55") (name "Net-(U2C--)") (class "Default")
      (node (ref "R10") (pin "1") (pinfunction "1_1") (pintype "passive"))
      (node (ref "R34") (pin "2") (pinfunction "2_2") (pintype "passive"))
      (node (ref "R35") (pin "2") (pinfunction "2_2") (pintype "passive"))
      (node (ref "U2") (pin "8") (pinfunction "-_8") (pintype "bidirectional"))
    )
    (net (code "56") (name "Net-(U2D--)") (class "Default")
      (node (ref "R38") (pin "1") (pinfunction "1_1") (pintype "passive"))
      (node (ref "R39") (pin "1") (pinfunction "1_1") (pintype "passive"))
      (node (ref "R6") (pin "1") (pinfunction "1_1") (pintype "passive"))
      (node (ref "U2") (pin "12") (pinfunction "-_12") (pintype "bidirectional"))
    )
    (net (code "57") (name "Net-(U3-AI)") (class "Default")
      (node (ref "L1") (pin "1") (pinfunction "1_1") (pintype "bidirectional"))
      (node (ref "U3") (pin "5") (pinfunction "AI_5") (pintype "input"))
    )
    (net (code "58") (name "Net-(U3-AO)") (class "Default")
      (node (ref "U3") (pin "3") (pinfunction "AO_3") (pintype "output"))
      (node (ref "U5") (pin "1") (pinfunction "INPUT_1") (pintype "input"))
    )
    (net (code "59") (name "Net-(U5-OUTPUT)") (class "Default")
      (node (ref "U5") (pin "4") (pinfunction "OUTPUT_4") (pintype "bidirectional"))
      (node (ref "U8") (pin "11") (pinfunction "RF_IN_11") (pintype "bidirectional"))
    )
    (net (code "60") (name "Net-(U9-SRT)") (class "Default")
      (node (ref "C17") (pin "1") (pinfunction "1_1") (pintype "bidirectional"))
      (node (ref "U9") (pin "3") (pinfunction "SRT_3") (pintype "bidirectional"))
    )
    (net (code "61") (name "Net-(U9-SWT)") (class "Default")
      (node (ref "C22") (pin "1") (pinfunction "1_1") (pintype "bidirectional"))
      (node (ref "U9") (pin "2") (pinfunction "SWT_2") (pintype "bidirectional"))
    )
    (net (code "62") (name "Net-(U10-P0)") (class "Default")
      (node (ref "R8") (pin "2") (pinfunction "2_2") (pintype "passive"))
      (node (ref "U10") (pin "2") (pinfunction "P0_2") (pintype "bidirectional"))
    )
    (net (code "63") (name "Net-(U10-P1)") (class "Default")
      (node (ref "R4") (pin "2") (pinfunction "2_2") (pintype "passive"))
      (node (ref "U10") (pin "3") (pinfunction "P1_3") (pintype "bidirectional"))
    )
    (net (code "64") (name "Net-(U10-P2)") (class "Default")
      (node (ref "R5") (pin "2") (pinfunction "2_2") (pintype "passive"))
      (node (ref "U10") (pin "4") (pinfunction "P2_4") (pintype "bidirectional"))
    )
    (net (code "65") (name "Net-(U15-PC14{slash}OSC32IN)") (class "Default")
      (node (ref "C1") (pin "2") (pinfunction "2_2") (pintype "bidirectional"))
      (node (ref "U15") (pin "2") (pinfunction "PC14/OSC32IN_2") (pintype "bidirectional"))
      (node (ref "X1") (pin "B") (pinfunction "2_B") (pintype "bidirectional"))
    )
    (net (code "66") (name "Net-(U15-PC15{slash}OSC32OUT)") (class "Default")
      (node (ref "C2") (pin "2") (pinfunction "2_2") (pintype "bidirectional"))
      (node (ref "U15") (pin "3") (pinfunction "PC15/OSC32OUT_3") (pintype "bidirectional"))
      (node (ref "X1") (pin "A") (pinfunction "1_A") (pintype "bidirectional"))
    )
    (net (code "67") (name "PARTICLE_RST") (class "Default")
      (node (ref "ASSY1") (pin "D2") (pinfunction "D2_D2") (pintype "bidirectional"))
      (node (ref "Q1") (pin "1") (pinfunction "G_1") (pintype "passive"))
      (node (ref "R44") (pin "1") (pinfunction "1_1") (pintype "passive"))
    )
    (net (code "68") (name "REF_1V5") (class "Default")
      (node (ref "C10") (pin "1") (pinfunction "1_1") (pintype "bidirectional"))
      (node (ref "C11") (pin "1") (pinfunction "1_1") (pintype "bidirectional"))
      (node (ref "C12") (pin "1") (pinfunction "1_1") (pintype "bidirectional"))
      (node (ref "C13") (pin "1") (pinfunction "1_1") (pintype "bidirectional"))
      (node (ref "U11") (pin "1") (pinfunction "VBIAS_1") (pintype "input"))
      (node (ref "U2") (pin "11") (pinfunction "+_11") (pintype "bidirectional"))
      (node (ref "U2") (pin "2") (pinfunction "+_2") (pintype "bidirectional"))
      (node (ref "U2") (pin "4") (pinfunction "+_4") (pintype "bidirectional"))
      (node (ref "U2") (pin "9") (pinfunction "+_9") (pintype "bidirectional"))
    )
    (net (code "69") (name "REF_3V") (class "Default")
      (node (ref "C14") (pin "1") (pinfunction "1_1") (pintype "bidirectional"))
      (node (ref "C19") (pin "1") (pinfunction "1_1") (pintype "bidirectional"))
      (node (ref "U11") (pin "5") (pinfunction "VREF_5") (pintype "output"))
      (node (ref "U15") (pin "5") (pinfunction "VDDA/VREF_5") (pintype "bidirectional"))
      (node (ref "U2") (pin "3") (pinfunction "V+_3") (pintype "bidirectional"))
    )
    (net (code "70") (name "SD_ENABLE") (class "Default")
      (node (ref "ASSY1") (pin "C2") (pinfunction "C2_C2") (pintype "bidirectional"))
      (node (ref "R27") (pin "2") (pinfunction "2_2") (pintype "passive"))
      (node (ref "U13") (pin "3") (pinfunction "EN_3") (pintype "bidirectional"))
    )
    (net (code "71") (name "SD_MISO") (class "Default")
      (node (ref "ASSY1") (pin "A4") (pinfunction "A4_A4") (pintype "bidirectional"))
      (node (ref "J1") (pin "7") (pinfunction "DATA0/MISO_7") (pintype "bidirectional"))
      (node (ref "R16") (pin "1") (pinfunction "1_1") (pintype "passive"))
      (node (ref "U1") (pin "6") (pinfunction "SDO_6") (pintype "bidirectional"))
    )
    (net (code "72") (name "SD_MOSI") (class "Default")
      (node (ref "ASSY1") (pin "A5") (pinfunction "A5_A5") (pintype "bidirectional"))
      (node (ref "J1") (pin "3") (pinfunction "CMD/MOSI_3") (pintype "bidirectional"))
      (node (ref "R14") (pin "1") (pinfunction "1_1") (pintype "passive"))
      (node (ref "U1") (pin "9") (pinfunction "SDI_9") (pintype "bidirectional"))
    )
    (net (code "73") (name "SD_SCLK") (class "Default")
      (node (ref "ASSY1") (pin "A3") (pinfunction "A3_A3") (pintype "bidirectional"))
      (node (ref "J1") (pin "5") (pinfunction "CLK_5") (pintype "bidirectional"))
      (node (ref "U1") (pin "7") (pinfunction "SCL_7") (pintype "bidirectional"))
    )
    (net (code "74") (name "SENSORS_SCL") (class "Default")
      (node (ref "ASSY1") (pin "D1") (pinfunction "D1_D1") (pintype "bidirectional"))
      (node (ref "R17") (pin "1") (pinfunction "1_1") (pintype "passive"))
      (node (ref "U10") (pin "12") (pinfunction "SCL_12") (pintype "input"))
      (node (ref "U16") (pin "8") (pinfunction "SCL_B_8") (pintype "bidirectional"))
      (node (ref "U7") (pin "1") (pinfunction "SCL/SPC_1") (pintype "bidirectional"))
    )
    (net (code "75") (name "SENSORS_SDA") (class "Default")
      (node (ref "ASSY1") (pin "D0") (pinfunction "D0_D0") (pintype "bidirectional"))
      (node (ref "R13") (pin "1") (pinfunction "1_1") (pintype "passive"))
      (node (ref "U10") (pin "13") (pinfunction "SDA_13") (pintype "bidirectional"))
      (node (ref "U16") (pin "1") (pinfunction "SDA_B_1") (pintype "bidirectional"))
      (node (ref "U7") (pin "4") (pinfunction "MOSI/SDA_4") (pintype "bidirectional"))
    )
    (net (code "76") (name "SERIAL_NUM") (class "Default")
      (node (ref "ASSY1") (pin "B0") (pinfunction "B0_B0") (pintype "bidirectional"))
      (node (ref "R12") (pin "2") (pinfunction "2_2") (pintype "passive"))
      (node (ref "U4") (pin "2") (pinfunction "DATA_2") (pintype "input"))
    )
    (net (code "77") (name "SWDCLK") (class "Default")
      (node (ref "J2") (pin "4") (pinfunction "SWDCLK_4") (pintype "bidirectional"))
      (node (ref "U15") (pin "24") (pinfunction "PA14/SWDCLK_24") (pintype "bidirectional"))
    )
    (net (code "78") (name "SWDIO") (class "Default")
      (node (ref "J2") (pin "2") (pinfunction "SWDIO_2") (pintype "bidirectional"))
      (node (ref "U15") (pin "23") (pinfunction "PA13/SWDIO_23") (pintype "bidirectional"))
    )
    (net (code "79") (name "VCC") (class "Default")
      (node (ref "ASSY1") (pin "3V3") (pinfunction "3V3_3V3") (pintype "power_in"))
      (node (ref "C18") (pin "1") (pinfunction "1_1") (pintype "bidirectional"))
      (node (ref "C25") (pin "1") (pinfunction "1_1") (pintype "bidirectional"))
      (node (ref "C9") (pin "1") (pinfunction "1_1") (pintype "bidirectional"))
      (node (ref "D29") (pin "1") (pinfunction "VDD_1") (pintype "bidirectional"))
      (node (ref "Q2") (pin "2") (pinfunction "S_2") (pintype "passive"))
      (node (ref "R12") (pin "1") (pinfunction "1_1") (pintype "passive"))
      (node (ref "R13") (pin "2") (pinfunction "2_2") (pintype "passive"))
      (node (ref "R17") (pin "2") (pinfunction "2_2") (pintype "passive"))
      (node (ref "R19") (pin "1") (pinfunction "1_1") (pintype "passive"))
      (node (ref "R20") (pin "1") (pinfunction "1_1") (pintype "passive"))
      (node (ref "R32") (pin "1") (pinfunction "1_1") (pintype "passive"))
      (node (ref "U1") (pin "13") (pinfunction "VCC_13") (pintype "bidirectional"))
      (node (ref "U10") (pin "1") (pinfunction "AD2_1") (pintype "input"))
      (node (ref "U10") (pin "14") (pinfunction "V+_14") (pintype "power_in"))
      (node (ref "U10") (pin "15") (pinfunction "AD0_15") (pintype "input"))
      (node (ref "U10") (pin "16") (pinfunction "AD1_16") (pintype "input"))
      (node (ref "U12") (pin "5") (pinfunction "VSUPP_5") (pintype "bidirectional"))
      (node (ref "U12") (pin "6") (pinfunction "VSUPP_6") (pintype "bidirectional"))
      (node (ref "U13") (pin "5") (pinfunction "VSUPP_5") (pintype "bidirectional"))
      (node (ref "U13") (pin "6") (pinfunction "VSUPP_6") (pintype "bidirectional"))
      (node (ref "U14") (pin "5") (pinfunction "VSUPP_5") (pintype "bidirectional"))
      (node (ref "U14") (pin "6") (pinfunction "VSUPP_6") (pintype "bidirectional"))
      (node (ref "U16") (pin "7") (pinfunction "VCCB_7") (pintype "power_in"))
      (node (ref "U7") (pin "10") (pinfunction "VDD_IO_10") (pintype "bidirectional"))
      (node (ref "U7") (pin "2") (pinfunction "CS_2") (pintype "bidirectional"))
      (node (ref "U7") (pin "9") (pinfunction "VCC_9") (pintype "bidirectional"))
    )
    (net (code "80") (name "VCC_RF") (class "Default")
      (node (ref "C4") (pin "2") (pinfunction "2_2") (pintype "bidirectional"))
      (node (ref "U3") (pin "2") (pinfunction "VCC_2") (pintype "power_in"))
      (node (ref "U3") (pin "6") (pinfunction "PON_6") (pintype "input"))
      (node (ref "U8") (pin "14") (pinfunction "VCC_RF_14") (pintype "bidirectional"))
    )
    (net (code "81") (name "VOLTAGE_COPROC_RX") (class "Default")
      (node (ref "ASSY1") (pin "C1") (pinfunction "C1_C1") (pintype "bidirectional"))
      (node (ref "U15") (pin "30") (pinfunction "PB7_30") (pintype "bidirectional"))
    )
    (net (code "82") (name "VOLTAGE_COPROC_TX") (class "Default")
      (node (ref "ASSY1") (pin "C0") (pinfunction "C0_C0") (pintype "bidirectional"))
      (node (ref "U15") (pin "29") (pinfunction "PB6_29") (pintype "bidirectional"))
    )
    (net (code "83") (name "WDI") (class "Default")
      (node (ref "ASSY1") (pin "DAC") (pinfunction "DAC_DAC") (pintype "bidirectional"))
      (node (ref "R18") (pin "1") (pinfunction "1_1") (pintype "passive"))
      (node (ref "U1") (pin "2") (pinfunction "WDI_2") (pintype "bidirectional"))
      (node (ref "U9") (pin "6") (pinfunction "WDI_6") (pintype "bidirectional"))
    )
    (net (code "84") (name "unconnected-(ASSY1-PadVBAT)") (class "Default")
      (node (ref "ASSY1") (pin "VBAT") (pinfunction "VBAT_VBAT") (pintype "passive"))
    )
    (net (code "85") (name "unconnected-(J1-DATA1{slash}RSV-Pad8)") (class "Default")
      (node (ref "J1") (pin "8") (pinfunction "DATA1/RSV_8") (pintype "bidirectional"))
    )
    (net (code "86") (name "unconnected-(J1-DATA2{slash}NC-Pad1)") (class "Default")
      (node (ref "J1") (pin "1") (pinfunction "DATA2/NC_1") (pintype "bidirectional"))
    )
    (net (code "87") (name "unconnected-(J2-SWO-Pad6)") (class "Default")
      (node (ref "J2") (pin "6") (pinfunction "SWO_6") (pintype "bidirectional"))
    )
    (net (code "88") (name "unconnected-(U1-CLKOUT{slash}~{IRQ3}-Pad8)") (class "Default")
      (node (ref "U1") (pin "8") (pinfunction "CLKOUT/~{IRQ3}_8") (pintype "bidirectional"))
    )
    (net (code "89") (name "unconnected-(U1-~{RST}-Pad1)") (class "Default")
      (node (ref "U1") (pin "1") (pinfunction "~{RST}_1") (pintype "bidirectional"))
    )
    (net (code "90") (name "unconnected-(U4-NC-Pad6)") (class "Default")
      (node (ref "U4") (pin "6") (pinfunction "NC_6") (pintype "no_connect"))
    )
    (net (code "91") (name "unconnected-(U4-NC_2-Pad3)") (class "Default")
      (node (ref "U4") (pin "3") (pinfunction "NC_2_3") (pintype "no_connect"))
    )
    (net (code "92") (name "unconnected-(U4-NC_3-Pad4)") (class "Default")
      (node (ref "U4") (pin "4") (pinfunction "NC_3_4") (pintype "no_connect"))
    )
    (net (code "93") (name "unconnected-(U4-NC_4-Pad5)") (class "Default")
      (node (ref "U4") (pin "5") (pinfunction "NC_4_5") (pintype "no_connect"))
    )
    (net (code "94") (name "unconnected-(U7-INT2-Pad11)") (class "Default")
      (node (ref "U7") (pin "11") (pinfunction "INT2_11") (pintype "bidirectional"))
    )
    (net (code "95") (name "unconnected-(U8-EXTINT-Pad5)") (class "Default")
      (node (ref "U8") (pin "5") (pinfunction "EXTINT_5") (pintype "bidirectional"))
    )
    (net (code "96") (name "unconnected-(U8-LNA_EN-Pad13)") (class "Default")
      (node (ref "U8") (pin "13") (pinfunction "LNA_EN_13") (pintype "bidirectional"))
    )
    (net (code "97") (name "unconnected-(U8-SCL-Pad17)") (class "Default")
      (node (ref "U8") (pin "17") (pinfunction "SCL_17") (pintype "bidirectional"))
    )
    (net (code "98") (name "unconnected-(U8-SDA-Pad16)") (class "Default")
      (node (ref "U8") (pin "16") (pinfunction "SDA_16") (pintype "bidirectional"))
    )
    (net (code "99") (name "unconnected-(U8-V_ANT-Pad15)") (class "Default")
      (node (ref "U8") (pin "15") (pinfunction "V_ANT_15") (pintype "bidirectional"))
    )
    (net (code "100") (name "unconnected-(U8-~{RESET}-Pad9)") (class "Default")
      (node (ref "U8") (pin "9") (pinfunction "~{RESET}_9") (pintype "bidirectional"))
    )
    (net (code "101") (name "unconnected-(U8-~{SAFEBOOT}-Pad18)") (class "Default")
      (node (ref "U8") (pin "18") (pinfunction "~{SAFEBOOT}_18") (pintype "bidirectional"))
    )
    (net (code "102") (name "unconnected-(U10-P3-Pad5)") (class "Default")
      (node (ref "U10") (pin "5") (pinfunction "P3_5") (pintype "bidirectional"))
    )
    (net (code "103") (name "unconnected-(U10-P4-Pad7)") (class "Default")
      (node (ref "U10") (pin "7") (pinfunction "P4_7") (pintype "bidirectional"))
    )
    (net (code "104") (name "unconnected-(U10-P5-Pad8)") (class "Default")
      (node (ref "U10") (pin "8") (pinfunction "P5_8") (pintype "bidirectional"))
    )
    (net (code "105") (name "unconnected-(U10-P6-Pad9)") (class "Default")
      (node (ref "U10") (pin "9") (pinfunction "P6_9") (pintype "bidirectional"))
    )
    (net (code "106") (name "unconnected-(U10-P7-Pad10)") (class "Default")
      (node (ref "U10") (pin "10") (pinfunction "P7_10") (pintype "bidirectional"))
    )
    (net (code "107") (name "unconnected-(U10-~{INT{slash}08}-Pad11)") (class "Default")
      (node (ref "U10") (pin "11") (pinfunction "~{INT/08}_11") (pintype "output"))
    )
    (net (code "108") (name "unconnected-(U15-PA2-Pad8)") (class "Default")
      (node (ref "U15") (pin "8") (pinfunction "PA2_8") (pintype "bidirectional"))
    )
    (net (code "109") (name "unconnected-(U15-PA5-Pad11)") (class "Default")
      (node (ref "U15") (pin "11") (pinfunction "PA5_11") (pintype "bidirectional"))
    )
    (net (code "110") (name "unconnected-(U15-PA6-Pad12)") (class "Default")
      (node (ref "U15") (pin "12") (pinfunction "PA6_12") (pintype "bidirectional"))
    )
    (net (code "111") (name "unconnected-(U15-PA7-Pad13)") (class "Default")
      (node (ref "U15") (pin "13") (pinfunction "PA7_13") (pintype "bidirectional"))
    )
    (net (code "112") (name "unconnected-(U15-PA8-Pad18)") (class "Default")
      (node (ref "U15") (pin "18") (pinfunction "PA8_18") (pintype "bidirectional"))
    )
    (net (code "113") (name "unconnected-(U15-PA11-Pad21)") (class "Default")
      (node (ref "U15") (pin "21") (pinfunction "PA11_21") (pintype "bidirectional"))
    )
    (net (code "114") (name "unconnected-(U15-PA12-Pad22)") (class "Default")
      (node (ref "U15") (pin "22") (pinfunction "PA12_22") (pintype "bidirectional"))
    )
    (net (code "115") (name "unconnected-(U15-PA15{slash}JTDI-Pad25)") (class "Default")
      (node (ref "U15") (pin "25") (pinfunction "PA15/JTDI_25") (pintype "bidirectional"))
    )
    (net (code "116") (name "unconnected-(U15-PB0-Pad14)") (class "Default")
      (node (ref "U15") (pin "14") (pinfunction "PB0_14") (pintype "bidirectional"))
    )
    (net (code "117") (name "unconnected-(U17-NR-Pad4)") (class "Default")
      (node (ref "U17") (pin "4") (pinfunction "NR_4") (pintype "passive"))
    )
    (net (code "118") (name "~{EXTERNAL_RST}") (class "Default")
      (node (ref "ASSY1") (pin "RST") (pinfunction "RST_RST") (pintype "bidirectional"))
      (node (ref "R21") (pin "2") (pinfunction "2_2") (pintype "passive"))
      (node (ref "U9") (pin "7") (pinfunction "~{RESET}_7") (pintype "bidirectional"))
    )
    (net (code "119") (name "~{RST}") (class "Default")
      (node (ref "J2") (pin "3") (pinfunction "~{RESET}_3") (pintype "bidirectional"))
      (node (ref "S1") (pin "2") (pinfunction "P$2_2") (pintype "passive"))
      (node (ref "U15") (pin "4") (pinfunction "~{RST}_4") (pintype "bidirectional"))
    )
    (net (code "120") (name "~{RTC_CS}") (class "Default")
      (node (ref "ASSY1") (pin "C5") (pinfunction "C5_C5") (pintype "bidirectional"))
      (node (ref "R20") (pin "2") (pinfunction "2_2") (pintype "passive"))
      (node (ref "R22") (pin "2") (pinfunction "2_2") (pintype "passive"))
      (node (ref "U1") (pin "12") (pinfunction "~{CS}_12") (pintype "bidirectional"))
    )
    (net (code "121") (name "~{RTC_INT1}") (class "Default")
      (node (ref "ASSY1") (pin "D5") (pinfunction "D5_D5") (pintype "bidirectional"))
      (node (ref "R19") (pin "2") (pinfunction "2_2") (pintype "passive"))
      (node (ref "U1") (pin "11") (pinfunction "FOUT/~{IRQ1}_11") (pintype "bidirectional"))
    )
    (net (code "122") (name "~{RTC_INT2}") (class "Default")
      (node (ref "ASSY1") (pin "D3") (pinfunction "D3_D3") (pintype "bidirectional"))
      (node (ref "Q2") (pin "1") (pinfunction "G_1") (pintype "passive"))
      (node (ref "R32") (pin "2") (pinfunction "2_2") (pintype "passive"))
      (node (ref "U1") (pin "4") (pinfunction "~{IRQ2}_4") (pintype "bidirectional"))
    )
    (net (code "123") (name "~{SD_CS}") (class "Default")
      (node (ref "ASSY1") (pin "A2") (pinfunction "A2_A2") (pintype "bidirectional"))
      (node (ref "J1") (pin "2") (pinfunction "DATA3-CD/CS_N_2") (pintype "bidirectional"))
      (node (ref "R15") (pin "1") (pinfunction "1_1") (pintype "passive"))
    )
    (net (code "124") (name "~{SD_DETECT}") (class "Default")
      (node (ref "ASSY1") (pin "D6") (pinfunction "D6_D6") (pintype "bidirectional"))
      (node (ref "J1") (pin "A") (pinfunction "A_A") (pintype "bidirectional"))
      (node (ref "R26") (pin "1") (pinfunction "1_1") (pintype "passive"))
    )
  )
)
